# M8320D.net
KiCad netlist of a schematic drawn in EAGLE
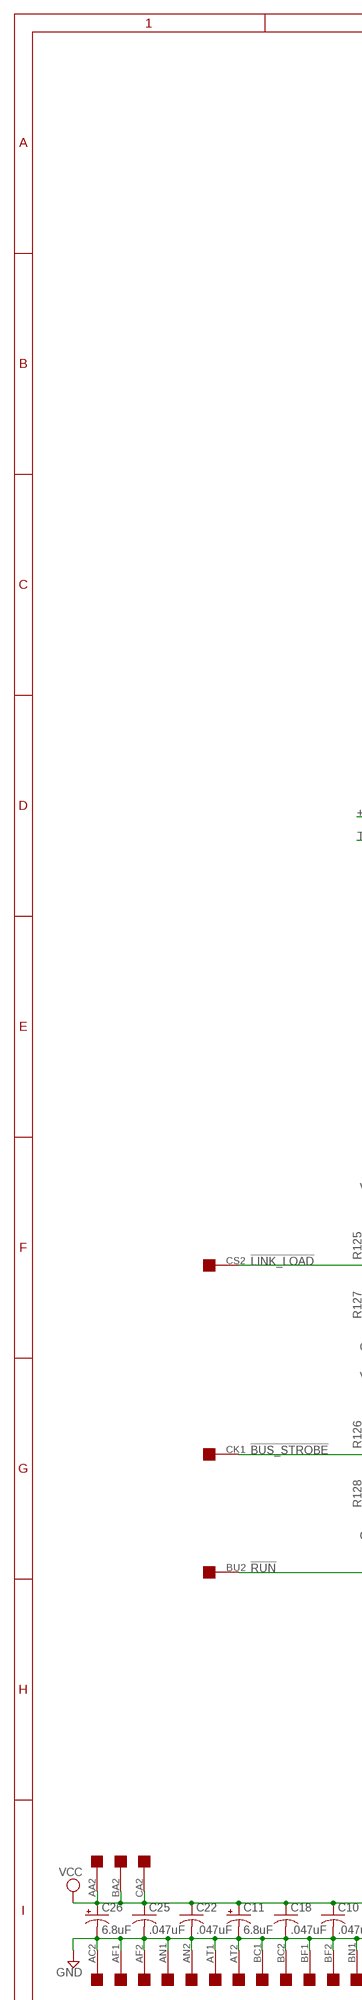
[diagram p0: schematic, sheet 1, part 1 of 2]
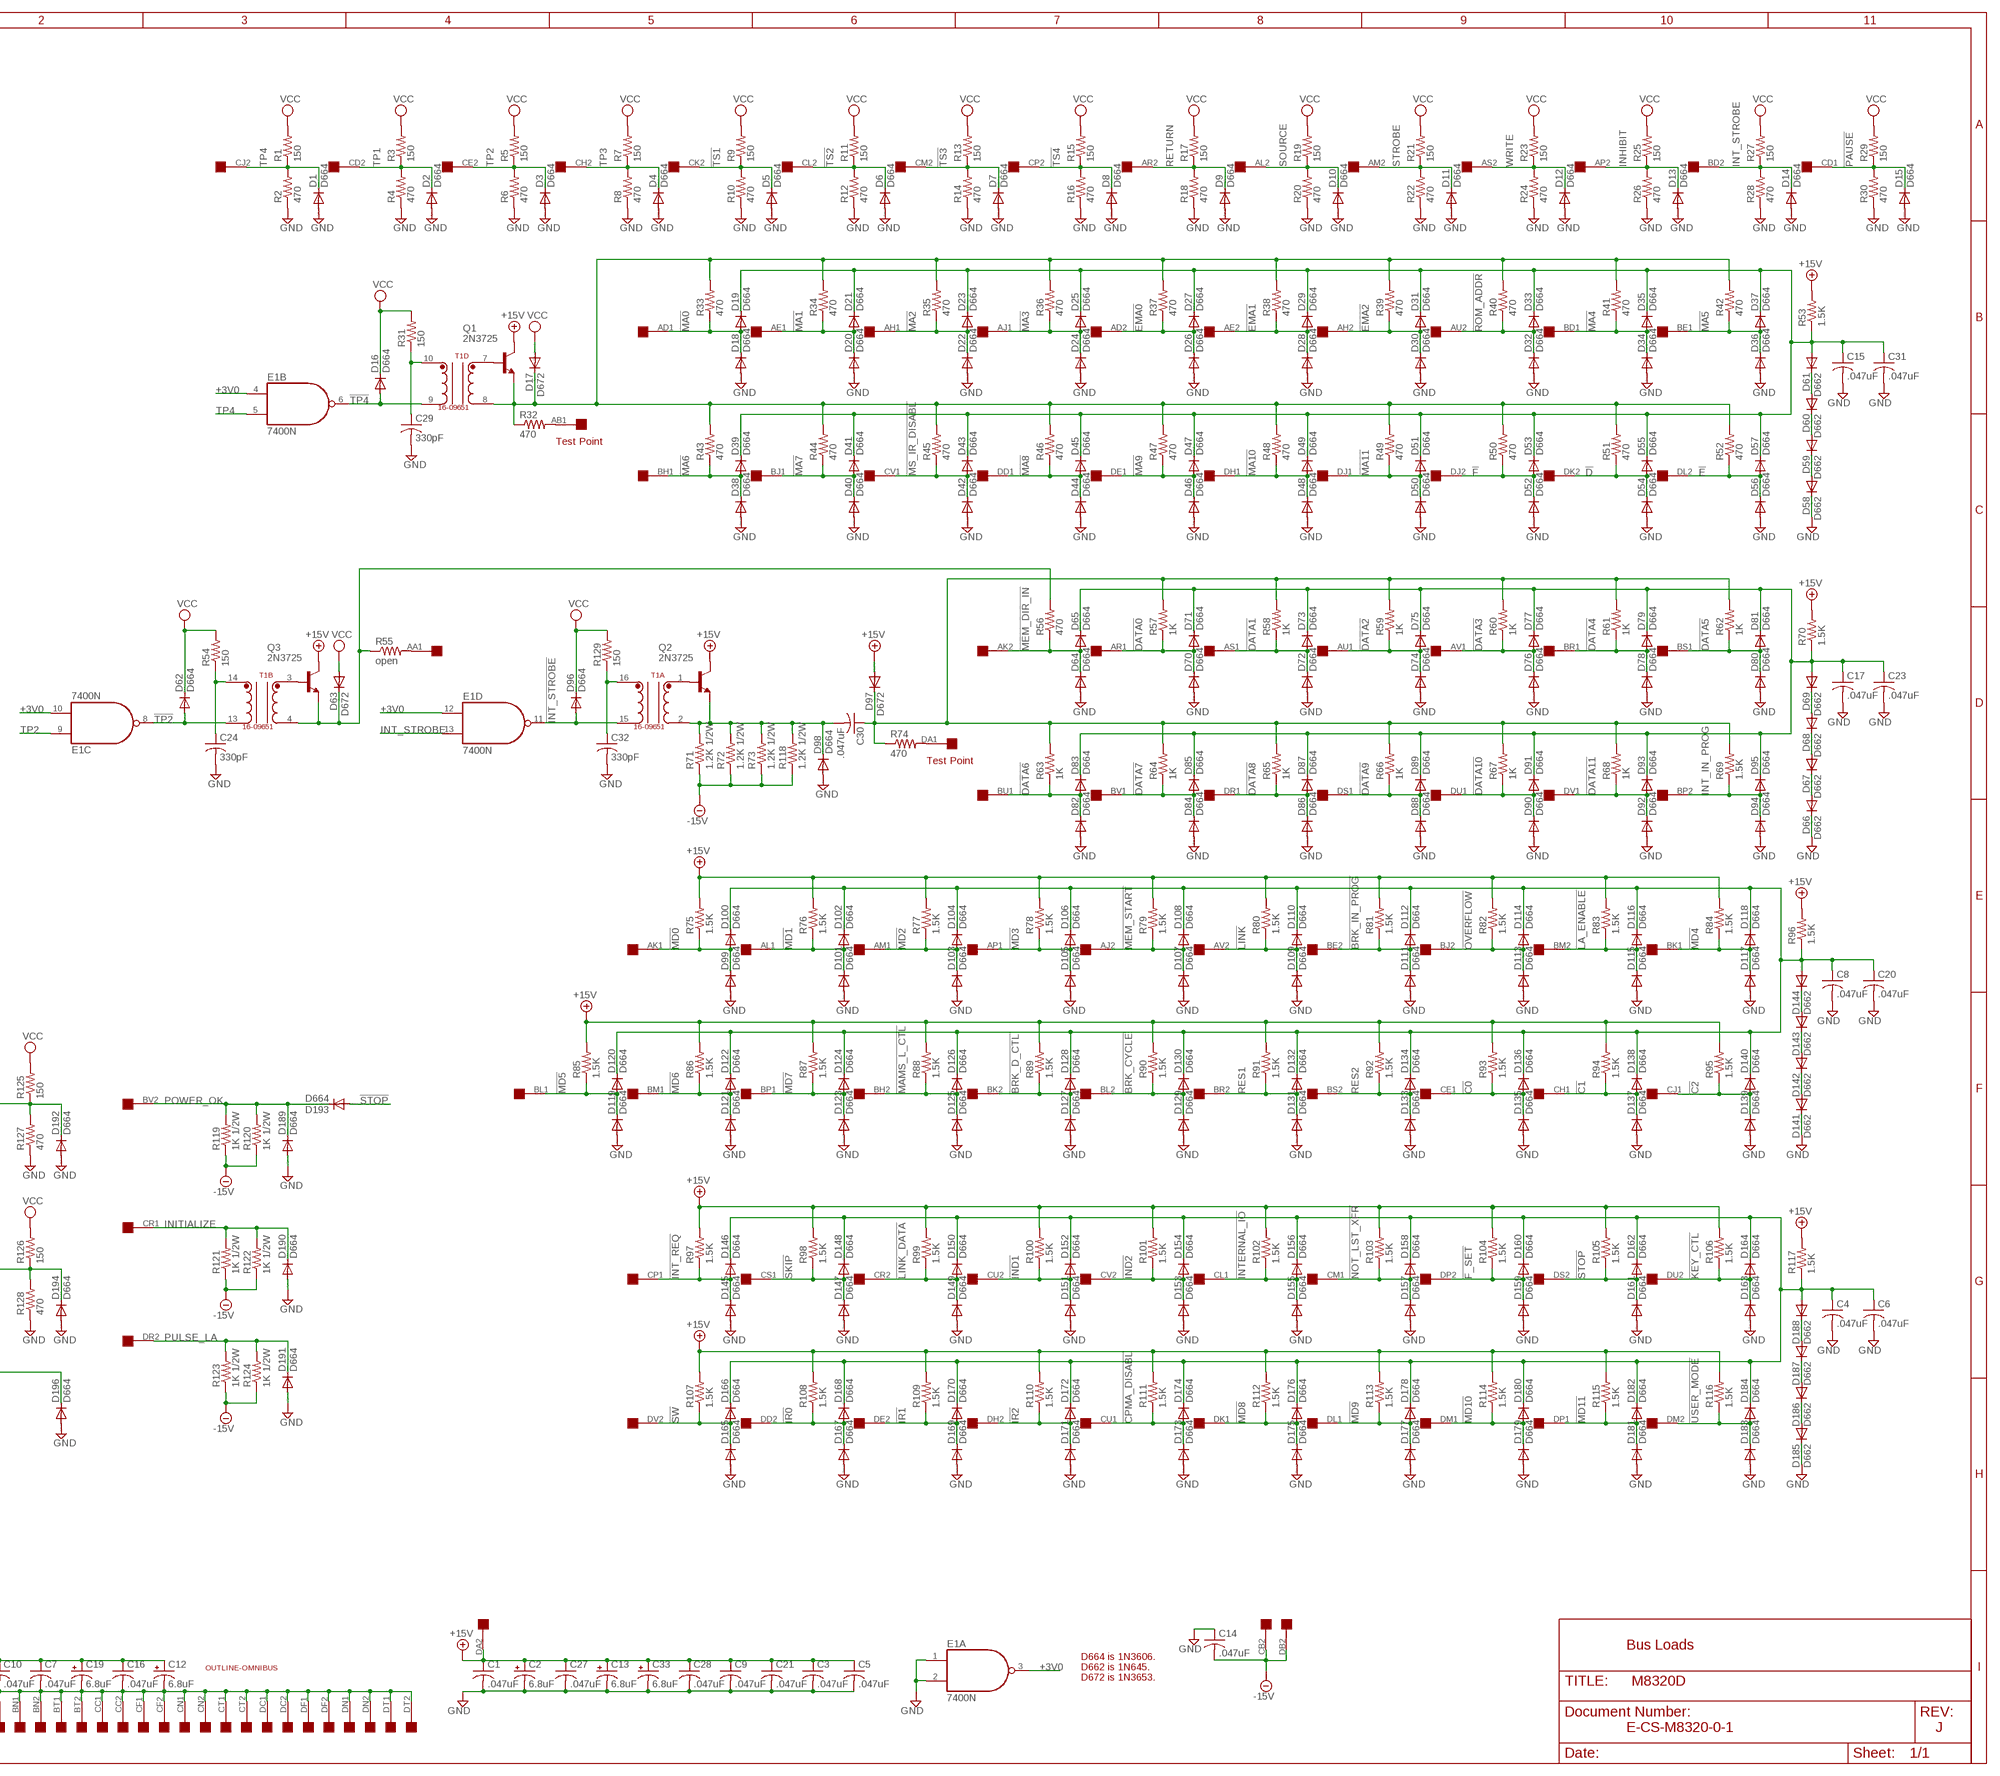
[diagram p1: schematic, sheet 1, part 2 of 2]

(export (version "E")
  (design (tool "Eeschema 10.0.6"))
  (components
    (comp (ref "C1")
      (value ".047uF")
      (footprint "eagle-import:C063-025X075")
      (libsource (lib "eagle-import") (part "C-US"))
    )
    (comp (ref "C2")
      (value "6.8uF")
      (footprint "eagle-import:E12-8")
      (libsource (lib "eagle-import") (part "CPOL-USE20-8AXIAL"))
    )
    (comp (ref "C3")
      (value ".047uF")
      (footprint "eagle-import:C063-025X075")
      (libsource (lib "eagle-import") (part "C-US"))
    )
    (comp (ref "C4")
      (value ".047uF")
      (footprint "eagle-import:C063-025X075")
      (libsource (lib "eagle-import") (part "C-US"))
    )
    (comp (ref "C5")
      (value ".047uF")
      (footprint "eagle-import:C063-025X075")
      (libsource (lib "eagle-import") (part "C-US"))
    )
    (comp (ref "C6")
      (value ".047uF")
      (footprint "eagle-import:C063-025X075")
      (libsource (lib "eagle-import") (part "C-US"))
    )
    (comp (ref "C7")
      (value ".047uF")
      (footprint "eagle-import:C063-025X075")
      (libsource (lib "eagle-import") (part "C-US"))
    )
    (comp (ref "C8")
      (value ".047uF")
      (footprint "eagle-import:C063-025X075")
      (libsource (lib "eagle-import") (part "C-US"))
    )
    (comp (ref "C9")
      (value ".047uF")
      (footprint "eagle-import:C063-025X075")
      (libsource (lib "eagle-import") (part "C-US"))
    )
    (comp (ref "C10")
      (value ".047uF")
      (footprint "eagle-import:C063-025X075")
      (libsource (lib "eagle-import") (part "C-US"))
    )
    (comp (ref "C11")
      (value "6.8uF")
      (footprint "eagle-import:E12-8")
      (libsource (lib "eagle-import") (part "CPOL-USE20-8AXIAL"))
    )
    (comp (ref "C12")
      (value "6.8uF")
      (footprint "eagle-import:E12-8")
      (libsource (lib "eagle-import") (part "CPOL-USE20-8AXIAL"))
    )
    (comp (ref "C13")
      (value "6.8uF")
      (footprint "eagle-import:E12-8")
      (libsource (lib "eagle-import") (part "CPOL-USE20-8AXIAL"))
    )
    (comp (ref "C14")
      (value ".047uF")
      (footprint "eagle-import:C063-025X075")
      (libsource (lib "eagle-import") (part "C-US"))
    )
    (comp (ref "C15")
      (value ".047uF")
      (footprint "eagle-import:C063-025X075")
      (libsource (lib "eagle-import") (part "C-US"))
    )
    (comp (ref "C16")
      (value ".047uF")
      (footprint "eagle-import:C063-025X075")
      (libsource (lib "eagle-import") (part "C-US"))
    )
    (comp (ref "C17")
      (value ".047uF")
      (footprint "eagle-import:C063-025X075")
      (libsource (lib "eagle-import") (part "C-US"))
    )
    (comp (ref "C18")
      (value ".047uF")
      (footprint "eagle-import:C063-025X075")
      (libsource (lib "eagle-import") (part "C-US"))
    )
    (comp (ref "C19")
      (value "6.8uF")
      (footprint "eagle-import:E12-8")
      (libsource (lib "eagle-import") (part "CPOL-USE20-8AXIAL"))
    )
    (comp (ref "C20")
      (value ".047uF")
      (footprint "eagle-import:C063-025X075")
      (libsource (lib "eagle-import") (part "C-US"))
    )
    (comp (ref "C21")
      (value ".047uF")
      (footprint "eagle-import:C063-025X075")
      (libsource (lib "eagle-import") (part "C-US"))
    )
    (comp (ref "C22")
      (value ".047uF")
      (footprint "eagle-import:C063-025X075")
      (libsource (lib "eagle-import") (part "C-US"))
    )
    (comp (ref "C23")
      (value ".047uF")
      (footprint "eagle-import:C063-025X075")
      (libsource (lib "eagle-import") (part "C-US"))
    )
    (comp (ref "C24")
      (value "330pF")
      (footprint "eagle-import:C063-025X075")
      (libsource (lib "eagle-import") (part "C-US"))
    )
    (comp (ref "C25")
      (value ".047uF")
      (footprint "eagle-import:C063-025X075")
      (libsource (lib "eagle-import") (part "C-US"))
    )
    (comp (ref "C26")
      (value "6.8uF")
      (footprint "eagle-import:E12-8")
      (libsource (lib "eagle-import") (part "CPOL-USE20-8AXIAL"))
    )
    (comp (ref "C27")
      (value ".047uF")
      (footprint "eagle-import:C063-025X075")
      (libsource (lib "eagle-import") (part "C-US"))
    )
    (comp (ref "C28")
      (value ".047uF")
      (footprint "eagle-import:C063-025X075")
      (libsource (lib "eagle-import") (part "C-US"))
    )
    (comp (ref "C29")
      (value "330pF")
      (footprint "eagle-import:C063-025X075")
      (libsource (lib "eagle-import") (part "C-US"))
    )
    (comp (ref "C30")
      (value ".047uF")
      (footprint "eagle-import:C063-025X075")
      (libsource (lib "eagle-import") (part "C-US"))
    )
    (comp (ref "C31")
      (value ".047uF")
      (footprint "eagle-import:C063-025X075")
      (libsource (lib "eagle-import") (part "C-US"))
    )
    (comp (ref "C32")
      (value "330pF")
      (footprint "eagle-import:C063-025X075")
      (libsource (lib "eagle-import") (part "C-US"))
    )
    (comp (ref "C33")
      (value "6.8uF")
      (footprint "eagle-import:E12-8")
      (libsource (lib "eagle-import") (part "CPOL-USE20-8AXIAL"))
    )
    (comp (ref "D1")
      (value "D664")
      (footprint "eagle-import:DO35-10")
      (libsource (lib "eagle-import") (part "DIODE-DO35-10"))
    )
    (comp (ref "D2")
      (value "D664")
      (footprint "eagle-import:DO35-10")
      (libsource (lib "eagle-import") (part "DIODE-DO35-10"))
    )
    (comp (ref "D3")
      (value "D664")
      (footprint "eagle-import:DO35-10")
      (libsource (lib "eagle-import") (part "DIODE-DO35-10"))
    )
    (comp (ref "D4")
      (value "D664")
      (footprint "eagle-import:DO35-10")
      (libsource (lib "eagle-import") (part "DIODE-DO35-10"))
    )
    (comp (ref "D5")
      (value "D664")
      (footprint "eagle-import:DO35-10")
      (libsource (lib "eagle-import") (part "DIODE-DO35-10"))
    )
    (comp (ref "D6")
      (value "D664")
      (footprint "eagle-import:DO35-10")
      (libsource (lib "eagle-import") (part "DIODE-DO35-10"))
    )
    (comp (ref "D7")
      (value "D664")
      (footprint "eagle-import:DO35-10")
      (libsource (lib "eagle-import") (part "DIODE-DO35-10"))
    )
    (comp (ref "D8")
      (value "D664")
      (footprint "eagle-import:DO35-10")
      (libsource (lib "eagle-import") (part "DIODE-DO35-10"))
    )
    (comp (ref "D9")
      (value "D664")
      (footprint "eagle-import:DO35-10")
      (libsource (lib "eagle-import") (part "DIODE-DO35-10"))
    )
    (comp (ref "D10")
      (value "D664")
      (footprint "eagle-import:DO35-10")
      (libsource (lib "eagle-import") (part "DIODE-DO35-10"))
    )
    (comp (ref "D11")
      (value "D664")
      (footprint "eagle-import:DO35-10")
      (libsource (lib "eagle-import") (part "DIODE-DO35-10"))
    )
    (comp (ref "D12")
      (value "D664")
      (footprint "eagle-import:DO35-10")
      (libsource (lib "eagle-import") (part "DIODE-DO35-10"))
    )
    (comp (ref "D13")
      (value "D664")
      (footprint "eagle-import:DO35-10")
      (libsource (lib "eagle-import") (part "DIODE-DO35-10"))
    )
    (comp (ref "D14")
      (value "D664")
      (footprint "eagle-import:DO35-10")
      (libsource (lib "eagle-import") (part "DIODE-DO35-10"))
    )
    (comp (ref "D15")
      (value "D664")
      (footprint "eagle-import:DO35-10")
      (libsource (lib "eagle-import") (part "DIODE-DO35-10"))
    )
    (comp (ref "D16")
      (value "D664")
      (footprint "eagle-import:DO35-10")
      (libsource (lib "eagle-import") (part "DIODE-DO35-10"))
    )
    (comp (ref "D17")
      (value "D672")
      (footprint "eagle-import:DO35-10")
      (libsource (lib "eagle-import") (part "DIODE-DO35-10"))
    )
    (comp (ref "D18")
      (value "D664")
      (footprint "eagle-import:DO35-10")
      (libsource (lib "eagle-import") (part "DIODE-DO35-10"))
    )
    (comp (ref "D19")
      (value "D664")
      (footprint "eagle-import:DO35-10")
      (libsource (lib "eagle-import") (part "DIODE-DO35-10"))
    )
    (comp (ref "D20")
      (value "D664")
      (footprint "eagle-import:DO35-10")
      (libsource (lib "eagle-import") (part "DIODE-DO35-10"))
    )
    (comp (ref "D21")
      (value "D664")
      (footprint "eagle-import:DO35-10")
      (libsource (lib "eagle-import") (part "DIODE-DO35-10"))
    )
    (comp (ref "D22")
      (value "D664")
      (footprint "eagle-import:DO35-10")
      (libsource (lib "eagle-import") (part "DIODE-DO35-10"))
    )
    (comp (ref "D23")
      (value "D664")
      (footprint "eagle-import:DO35-10")
      (libsource (lib "eagle-import") (part "DIODE-DO35-10"))
    )
    (comp (ref "D24")
      (value "D664")
      (footprint "eagle-import:DO35-10")
      (libsource (lib "eagle-import") (part "DIODE-DO35-10"))
    )
    (comp (ref "D25")
      (value "D664")
      (footprint "eagle-import:DO35-10")
      (libsource (lib "eagle-import") (part "DIODE-DO35-10"))
    )
    (comp (ref "D26")
      (value "D664")
      (footprint "eagle-import:DO35-10")
      (libsource (lib "eagle-import") (part "DIODE-DO35-10"))
    )
    (comp (ref "D27")
      (value "D664")
      (footprint "eagle-import:DO35-10")
      (libsource (lib "eagle-import") (part "DIODE-DO35-10"))
    )
    (comp (ref "D28")
      (value "D664")
      (footprint "eagle-import:DO35-10")
      (libsource (lib "eagle-import") (part "DIODE-DO35-10"))
    )
    (comp (ref "D29")
      (value "D664")
      (footprint "eagle-import:DO35-10")
      (libsource (lib "eagle-import") (part "DIODE-DO35-10"))
    )
    (comp (ref "D30")
      (value "D664")
      (footprint "eagle-import:DO35-10")
      (libsource (lib "eagle-import") (part "DIODE-DO35-10"))
    )
    (comp (ref "D31")
      (value "D664")
      (footprint "eagle-import:DO35-10")
      (libsource (lib "eagle-import") (part "DIODE-DO35-10"))
    )
    (comp (ref "D32")
      (value "D664")
      (footprint "eagle-import:DO35-10")
      (libsource (lib "eagle-import") (part "DIODE-DO35-10"))
    )
    (comp (ref "D33")
      (value "D664")
      (footprint "eagle-import:DO35-10")
      (libsource (lib "eagle-import") (part "DIODE-DO35-10"))
    )
    (comp (ref "D34")
      (value "D664")
      (footprint "eagle-import:DO35-10")
      (libsource (lib "eagle-import") (part "DIODE-DO35-10"))
    )
    (comp (ref "D35")
      (value "D664")
      (footprint "eagle-import:DO35-10")
      (libsource (lib "eagle-import") (part "DIODE-DO35-10"))
    )
    (comp (ref "D36")
      (value "D664")
      (footprint "eagle-import:DO35-10")
      (libsource (lib "eagle-import") (part "DIODE-DO35-10"))
    )
    (comp (ref "D37")
      (value "D664")
      (footprint "eagle-import:DO35-10")
      (libsource (lib "eagle-import") (part "DIODE-DO35-10"))
    )
    (comp (ref "D38")
      (value "D664")
      (footprint "eagle-import:DO35-10")
      (libsource (lib "eagle-import") (part "DIODE-DO35-10"))
    )
    (comp (ref "D39")
      (value "D664")
      (footprint "eagle-import:DO35-10")
      (libsource (lib "eagle-import") (part "DIODE-DO35-10"))
    )
    (comp (ref "D40")
      (value "D664")
      (footprint "eagle-import:DO35-10")
      (libsource (lib "eagle-import") (part "DIODE-DO35-10"))
    )
    (comp (ref "D41")
      (value "D664")
      (footprint "eagle-import:DO35-10")
      (libsource (lib "eagle-import") (part "DIODE-DO35-10"))
    )
    (comp (ref "D42")
      (value "D664")
      (footprint "eagle-import:DO35-10")
      (libsource (lib "eagle-import") (part "DIODE-DO35-10"))
    )
    (comp (ref "D43")
      (value "D664")
      (footprint "eagle-import:DO35-10")
      (libsource (lib "eagle-import") (part "DIODE-DO35-10"))
    )
    (comp (ref "D44")
      (value "D664")
      (footprint "eagle-import:DO35-10")
      (libsource (lib "eagle-import") (part "DIODE-DO35-10"))
    )
    (comp (ref "D45")
      (value "D664")
      (footprint "eagle-import:DO35-10")
      (libsource (lib "eagle-import") (part "DIODE-DO35-10"))
    )
    (comp (ref "D46")
      (value "D664")
      (footprint "eagle-import:DO35-10")
      (libsource (lib "eagle-import") (part "DIODE-DO35-10"))
    )
    (comp (ref "D47")
      (value "D664")
      (footprint "eagle-import:DO35-10")
      (libsource (lib "eagle-import") (part "DIODE-DO35-10"))
    )
    (comp (ref "D48")
      (value "D664")
      (footprint "eagle-import:DO35-10")
      (libsource (lib "eagle-import") (part "DIODE-DO35-10"))
    )
    (comp (ref "D49")
      (value "D664")
      (footprint "eagle-import:DO35-10")
      (libsource (lib "eagle-import") (part "DIODE-DO35-10"))
    )
    (comp (ref "D50")
      (value "D664")
      (footprint "eagle-import:DO35-10")
      (libsource (lib "eagle-import") (part "DIODE-DO35-10"))
    )
    (comp (ref "D51")
      (value "D664")
      (footprint "eagle-import:DO35-10")
      (libsource (lib "eagle-import") (part "DIODE-DO35-10"))
    )
    (comp (ref "D52")
      (value "D664")
      (footprint "eagle-import:DO35-10")
      (libsource (lib "eagle-import") (part "DIODE-DO35-10"))
    )
    (comp (ref "D53")
      (value "D664")
      (footprint "eagle-import:DO35-10")
      (libsource (lib "eagle-import") (part "DIODE-DO35-10"))
    )
    (comp (ref "D54")
      (value "D664")
      (footprint "eagle-import:DO35-10")
      (libsource (lib "eagle-import") (part "DIODE-DO35-10"))
    )
    (comp (ref "D55")
      (value "D664")
      (footprint "eagle-import:DO35-10")
      (libsource (lib "eagle-import") (part "DIODE-DO35-10"))
    )
    (comp (ref "D56")
      (value "D664")
      (footprint "eagle-import:DO35-10")
      (libsource (lib "eagle-import") (part "DIODE-DO35-10"))
    )
    (comp (ref "D57")
      (value "D664")
      (footprint "eagle-import:DO35-10")
      (libsource (lib "eagle-import") (part "DIODE-DO35-10"))
    )
    (comp (ref "D58")
      (value "D662")
      (footprint "eagle-import:DO35-10")
      (libsource (lib "eagle-import") (part "DIODE-DO35-10"))
    )
    (comp (ref "D59")
      (value "D662")
      (footprint "eagle-import:DO35-10")
      (libsource (lib "eagle-import") (part "DIODE-DO35-10"))
    )
    (comp (ref "D60")
      (value "D662")
      (footprint "eagle-import:DO35-10")
      (libsource (lib "eagle-import") (part "DIODE-DO35-10"))
    )
    (comp (ref "D61")
      (value "D662")
      (footprint "eagle-import:DO35-10")
      (libsource (lib "eagle-import") (part "DIODE-DO35-10"))
    )
    (comp (ref "D62")
      (value "D664")
      (footprint "eagle-import:DO35-10")
      (libsource (lib "eagle-import") (part "DIODE-DO35-10"))
    )
    (comp (ref "D63")
      (value "D672")
      (footprint "eagle-import:DO35-10")
      (libsource (lib "eagle-import") (part "DIODE-DO35-10"))
    )
    (comp (ref "D64")
      (value "D664")
      (footprint "eagle-import:DO35-10")
      (libsource (lib "eagle-import") (part "DIODE-DO35-10"))
    )
    (comp (ref "D65")
      (value "D664")
      (footprint "eagle-import:DO35-10")
      (libsource (lib "eagle-import") (part "DIODE-DO35-10"))
    )
    (comp (ref "D66")
      (value "D662")
      (footprint "eagle-import:DO35-10")
      (libsource (lib "eagle-import") (part "DIODE-DO35-10"))
    )
    (comp (ref "D67")
      (value "D662")
      (footprint "eagle-import:DO35-10")
      (libsource (lib "eagle-import") (part "DIODE-DO35-10"))
    )
    (comp (ref "D68")
      (value "D662")
      (footprint "eagle-import:DO35-10")
      (libsource (lib "eagle-import") (part "DIODE-DO35-10"))
    )
    (comp (ref "D69")
      (value "D662")
      (footprint "eagle-import:DO35-10")
      (libsource (lib "eagle-import") (part "DIODE-DO35-10"))
    )
    (comp (ref "D70")
      (value "D664")
      (footprint "eagle-import:DO35-10")
      (libsource (lib "eagle-import") (part "DIODE-DO35-10"))
    )
    (comp (ref "D71")
      (value "D664")
      (footprint "eagle-import:DO35-10")
      (libsource (lib "eagle-import") (part "DIODE-DO35-10"))
    )
    (comp (ref "D72")
      (value "D664")
      (footprint "eagle-import:DO35-10")
      (libsource (lib "eagle-import") (part "DIODE-DO35-10"))
    )
    (comp (ref "D73")
      (value "D664")
      (footprint "eagle-import:DO35-10")
      (libsource (lib "eagle-import") (part "DIODE-DO35-10"))
    )
    (comp (ref "D74")
      (value "D664")
      (footprint "eagle-import:DO35-10")
      (libsource (lib "eagle-import") (part "DIODE-DO35-10"))
    )
    (comp (ref "D75")
      (value "D664")
      (footprint "eagle-import:DO35-10")
      (libsource (lib "eagle-import") (part "DIODE-DO35-10"))
    )
    (comp (ref "D76")
      (value "D664")
      (footprint "eagle-import:DO35-10")
      (libsource (lib "eagle-import") (part "DIODE-DO35-10"))
    )
    (comp (ref "D77")
      (value "D664")
      (footprint "eagle-import:DO35-10")
      (libsource (lib "eagle-import") (part "DIODE-DO35-10"))
    )
    (comp (ref "D78")
      (value "D664")
      (footprint "eagle-import:DO35-10")
      (libsource (lib "eagle-import") (part "DIODE-DO35-10"))
    )
    (comp (ref "D79")
      (value "D664")
      (footprint "eagle-import:DO35-10")
      (libsource (lib "eagle-import") (part "DIODE-DO35-10"))
    )
    (comp (ref "D80")
      (value "D664")
      (footprint "eagle-import:DO35-10")
      (libsource (lib "eagle-import") (part "DIODE-DO35-10"))
    )
    (comp (ref "D81")
      (value "D664")
      (footprint "eagle-import:DO35-10")
      (libsource (lib "eagle-import") (part "DIODE-DO35-10"))
    )
    (comp (ref "D82")
      (value "D664")
      (footprint "eagle-import:DO35-10")
      (libsource (lib "eagle-import") (part "DIODE-DO35-10"))
    )
    (comp (ref "D83")
      (value "D664")
      (footprint "eagle-import:DO35-10")
      (libsource (lib "eagle-import") (part "DIODE-DO35-10"))
    )
    (comp (ref "D84")
      (value "D664")
      (footprint "eagle-import:DO35-10")
      (libsource (lib "eagle-import") (part "DIODE-DO35-10"))
    )
    (comp (ref "D85")
      (value "D664")
      (footprint "eagle-import:DO35-10")
      (libsource (lib "eagle-import") (part "DIODE-DO35-10"))
    )
    (comp (ref "D86")
      (value "D664")
      (footprint "eagle-import:DO35-10")
      (libsource (lib "eagle-import") (part "DIODE-DO35-10"))
    )
    (comp (ref "D87")
      (value "D664")
      (footprint "eagle-import:DO35-10")
      (libsource (lib "eagle-import") (part "DIODE-DO35-10"))
    )
    (comp (ref "D88")
      (value "D664")
      (footprint "eagle-import:DO35-10")
      (libsource (lib "eagle-import") (part "DIODE-DO35-10"))
    )
    (comp (ref "D89")
      (value "D664")
      (footprint "eagle-import:DO35-10")
      (libsource (lib "eagle-import") (part "DIODE-DO35-10"))
    )
    (comp (ref "D90")
      (value "D664")
      (footprint "eagle-import:DO35-10")
      (libsource (lib "eagle-import") (part "DIODE-DO35-10"))
    )
    (comp (ref "D91")
      (value "D664")
      (footprint "eagle-import:DO35-10")
      (libsource (lib "eagle-import") (part "DIODE-DO35-10"))
    )
    (comp (ref "D92")
      (value "D664")
      (footprint "eagle-import:DO35-10")
      (libsource (lib "eagle-import") (part "DIODE-DO35-10"))
    )
    (comp (ref "D93")
      (value "D664")
      (footprint "eagle-import:DO35-10")
      (libsource (lib "eagle-import") (part "DIODE-DO35-10"))
    )
    (comp (ref "D94")
      (value "D664")
      (footprint "eagle-import:DO35-10")
      (libsource (lib "eagle-import") (part "DIODE-DO35-10"))
    )
    (comp (ref "D95")
      (value "D664")
      (footprint "eagle-import:DO35-10")
      (libsource (lib "eagle-import") (part "DIODE-DO35-10"))
    )
    (comp (ref "D96")
      (value "D664")
      (footprint "eagle-import:DO35-10")
      (libsource (lib "eagle-import") (part "DIODE-DO35-10"))
    )
    (comp (ref "D97")
      (value "D672")
      (footprint "eagle-import:DO35-10")
      (libsource (lib "eagle-import") (part "DIODE-DO35-10"))
    )
    (comp (ref "D98")
      (value "D664")
      (footprint "eagle-import:DO35-10")
      (libsource (lib "eagle-import") (part "DIODE-DO35-10"))
    )
    (comp (ref "D99")
      (value "D664")
      (footprint "eagle-import:DO35-10")
      (libsource (lib "eagle-import") (part "DIODE-DO35-10"))
    )
    (comp (ref "D100")
      (value "D664")
      (footprint "eagle-import:DO35-10")
      (libsource (lib "eagle-import") (part "DIODE-DO35-10"))
    )
    (comp (ref "D101")
      (value "D664")
      (footprint "eagle-import:DO35-10")
      (libsource (lib "eagle-import") (part "DIODE-DO35-10"))
    )
    (comp (ref "D102")
      (value "D664")
      (footprint "eagle-import:DO35-10")
      (libsource (lib "eagle-import") (part "DIODE-DO35-10"))
    )
    (comp (ref "D103")
      (value "D664")
      (footprint "eagle-import:DO35-10")
      (libsource (lib "eagle-import") (part "DIODE-DO35-10"))
    )
    (comp (ref "D104")
      (value "D664")
      (footprint "eagle-import:DO35-10")
      (libsource (lib "eagle-import") (part "DIODE-DO35-10"))
    )
    (comp (ref "D105")
      (value "D664")
      (footprint "eagle-import:DO35-10")
      (libsource (lib "eagle-import") (part "DIODE-DO35-10"))
    )
    (comp (ref "D106")
      (value "D664")
      (footprint "eagle-import:DO35-10")
      (libsource (lib "eagle-import") (part "DIODE-DO35-10"))
    )
    (comp (ref "D107")
      (value "D664")
      (footprint "eagle-import:DO35-10")
      (libsource (lib "eagle-import") (part "DIODE-DO35-10"))
    )
    (comp (ref "D108")
      (value "D664")
      (footprint "eagle-import:DO35-10")
      (libsource (lib "eagle-import") (part "DIODE-DO35-10"))
    )
    (comp (ref "D109")
      (value "D664")
      (footprint "eagle-import:DO35-10")
      (libsource (lib "eagle-import") (part "DIODE-DO35-10"))
    )
    (comp (ref "D110")
      (value "D664")
      (footprint "eagle-import:DO35-10")
      (libsource (lib "eagle-import") (part "DIODE-DO35-10"))
    )
    (comp (ref "D111")
      (value "D664")
      (footprint "eagle-import:DO35-10")
      (libsource (lib "eagle-import") (part "DIODE-DO35-10"))
    )
    (comp (ref "D112")
      (value "D664")
      (footprint "eagle-import:DO35-10")
      (libsource (lib "eagle-import") (part "DIODE-DO35-10"))
    )
    (comp (ref "D113")
      (value "D664")
      (footprint "eagle-import:DO35-10")
      (libsource (lib "eagle-import") (part "DIODE-DO35-10"))
    )
    (comp (ref "D114")
      (value "D664")
      (footprint "eagle-import:DO35-10")
      (libsource (lib "eagle-import") (part "DIODE-DO35-10"))
    )
    (comp (ref "D115")
      (value "D664")
      (footprint "eagle-import:DO35-10")
      (libsource (lib "eagle-import") (part "DIODE-DO35-10"))
    )
    (comp (ref "D116")
      (value "D664")
      (footprint "eagle-import:DO35-10")
      (libsource (lib "eagle-import") (part "DIODE-DO35-10"))
    )
    (comp (ref "D117")
      (value "D664")
      (footprint "eagle-import:DO35-10")
      (libsource (lib "eagle-import") (part "DIODE-DO35-10"))
    )
    (comp (ref "D118")
      (value "D664")
      (footprint "eagle-import:DO35-10")
      (libsource (lib "eagle-import") (part "DIODE-DO35-10"))
    )
    (comp (ref "D119")
      (value "D664")
      (footprint "eagle-import:DO35-10")
      (libsource (lib "eagle-import") (part "DIODE-DO35-10"))
    )
    (comp (ref "D120")
      (value "D664")
      (footprint "eagle-import:DO35-10")
      (libsource (lib "eagle-import") (part "DIODE-DO35-10"))
    )
    (comp (ref "D121")
      (value "D664")
      (footprint "eagle-import:DO35-10")
      (libsource (lib "eagle-import") (part "DIODE-DO35-10"))
    )
    (comp (ref "D122")
      (value "D664")
      (footprint "eagle-import:DO35-10")
      (libsource (lib "eagle-import") (part "DIODE-DO35-10"))
    )
    (comp (ref "D123")
      (value "D664")
      (footprint "eagle-import:DO35-10")
      (libsource (lib "eagle-import") (part "DIODE-DO35-10"))
    )
    (comp (ref "D124")
      (value "D664")
      (footprint "eagle-import:DO35-10")
      (libsource (lib "eagle-import") (part "DIODE-DO35-10"))
    )
    (comp (ref "D125")
      (value "D664")
      (footprint "eagle-import:DO35-10")
      (libsource (lib "eagle-import") (part "DIODE-DO35-10"))
    )
    (comp (ref "D126")
      (value "D664")
      (footprint "eagle-import:DO35-10")
      (libsource (lib "eagle-import") (part "DIODE-DO35-10"))
    )
    (comp (ref "D127")
      (value "D664")
      (footprint "eagle-import:DO35-10")
      (libsource (lib "eagle-import") (part "DIODE-DO35-10"))
    )
    (comp (ref "D128")
      (value "D664")
      (footprint "eagle-import:DO35-10")
      (libsource (lib "eagle-import") (part "DIODE-DO35-10"))
    )
    (comp (ref "D129")
      (value "D664")
      (footprint "eagle-import:DO35-10")
      (libsource (lib "eagle-import") (part "DIODE-DO35-10"))
    )
    (comp (ref "D130")
      (value "D664")
      (footprint "eagle-import:DO35-10")
      (libsource (lib "eagle-import") (part "DIODE-DO35-10"))
    )
    (comp (ref "D131")
      (value "D664")
      (footprint "eagle-import:DO35-10")
      (libsource (lib "eagle-import") (part "DIODE-DO35-10"))
    )
    (comp (ref "D132")
      (value "D664")
      (footprint "eagle-import:DO35-10")
      (libsource (lib "eagle-import") (part "DIODE-DO35-10"))
    )
    (comp (ref "D133")
      (value "D664")
      (footprint "eagle-import:DO35-10")
      (libsource (lib "eagle-import") (part "DIODE-DO35-10"))
    )
    (comp (ref "D134")
      (value "D664")
      (footprint "eagle-import:DO35-10")
      (libsource (lib "eagle-import") (part "DIODE-DO35-10"))
    )
    (comp (ref "D135")
      (value "D664")
      (footprint "eagle-import:DO35-10")
      (libsource (lib "eagle-import") (part "DIODE-DO35-10"))
    )
    (comp (ref "D136")
      (value "D664")
      (footprint "eagle-import:DO35-10")
      (libsource (lib "eagle-import") (part "DIODE-DO35-10"))
    )
    (comp (ref "D137")
      (value "D664")
      (footprint "eagle-import:DO35-10")
      (libsource (lib "eagle-import") (part "DIODE-DO35-10"))
    )
    (comp (ref "D138")
      (value "D664")
      (footprint "eagle-import:DO35-10")
      (libsource (lib "eagle-import") (part "DIODE-DO35-10"))
    )
    (comp (ref "D139")
      (value "D664")
      (footprint "eagle-import:DO35-10")
      (libsource (lib "eagle-import") (part "DIODE-DO35-10"))
    )
    (comp (ref "D140")
      (value "D664")
      (footprint "eagle-import:DO35-10")
      (libsource (lib "eagle-import") (part "DIODE-DO35-10"))
    )
    (comp (ref "D141")
      (value "D662")
      (footprint "eagle-import:DO35-10")
      (libsource (lib "eagle-import") (part "DIODE-DO35-10"))
    )
    (comp (ref "D142")
      (value "D662")
      (footprint "eagle-import:DO35-10")
      (libsource (lib "eagle-import") (part "DIODE-DO35-10"))
    )
    (comp (ref "D143")
      (value "D662")
      (footprint "eagle-import:DO35-10")
      (libsource (lib "eagle-import") (part "DIODE-DO35-10"))
    )
    (comp (ref "D144")
      (value "D662")
      (footprint "eagle-import:DO35-10")
      (libsource (lib "eagle-import") (part "DIODE-DO35-10"))
    )
    (comp (ref "D145")
      (value "D664")
      (footprint "eagle-import:DO35-10")
      (libsource (lib "eagle-import") (part "DIODE-DO35-10"))
    )
    (comp (ref "D146")
      (value "D664")
      (footprint "eagle-import:DO35-10")
      (libsource (lib "eagle-import") (part "DIODE-DO35-10"))
    )
    (comp (ref "D147")
      (value "D664")
      (footprint "eagle-import:DO35-10")
      (libsource (lib "eagle-import") (part "DIODE-DO35-10"))
    )
    (comp (ref "D148")
      (value "D664")
      (footprint "eagle-import:DO35-10")
      (libsource (lib "eagle-import") (part "DIODE-DO35-10"))
    )
    (comp (ref "D149")
      (value "D664")
      (footprint "eagle-import:DO35-10")
      (libsource (lib "eagle-import") (part "DIODE-DO35-10"))
    )
    (comp (ref "D150")
      (value "D664")
      (footprint "eagle-import:DO35-10")
      (libsource (lib "eagle-import") (part "DIODE-DO35-10"))
    )
    (comp (ref "D151")
      (value "D664")
      (footprint "eagle-import:DO35-10")
      (libsource (lib "eagle-import") (part "DIODE-DO35-10"))
    )
    (comp (ref "D152")
      (value "D664")
      (footprint "eagle-import:DO35-10")
      (libsource (lib "eagle-import") (part "DIODE-DO35-10"))
    )
    (comp (ref "D153")
      (value "D664")
      (footprint "eagle-import:DO35-10")
      (libsource (lib "eagle-import") (part "DIODE-DO35-10"))
    )
    (comp (ref "D154")
      (value "D664")
      (footprint "eagle-import:DO35-10")
      (libsource (lib "eagle-import") (part "DIODE-DO35-10"))
    )
    (comp (ref "D155")
      (value "D664")
      (footprint "eagle-import:DO35-10")
      (libsource (lib "eagle-import") (part "DIODE-DO35-10"))
    )
    (comp (ref "D156")
      (value "D664")
      (footprint "eagle-import:DO35-10")
      (libsource (lib "eagle-import") (part "DIODE-DO35-10"))
    )
    (comp (ref "D157")
      (value "D664")
      (footprint "eagle-import:DO35-10")
      (libsource (lib "eagle-import") (part "DIODE-DO35-10"))
    )
    (comp (ref "D158")
      (value "D664")
      (footprint "eagle-import:DO35-10")
      (libsource (lib "eagle-import") (part "DIODE-DO35-10"))
    )
    (comp (ref "D159")
      (value "D664")
      (footprint "eagle-import:DO35-10")
      (libsource (lib "eagle-import") (part "DIODE-DO35-10"))
    )
    (comp (ref "D160")
      (value "D664")
      (footprint "eagle-import:DO35-10")
      (libsource (lib "eagle-import") (part "DIODE-DO35-10"))
    )
    (comp (ref "D161")
      (value "D664")
      (footprint "eagle-import:DO35-10")
      (libsource (lib "eagle-import") (part "DIODE-DO35-10"))
    )
    (comp (ref "D162")
      (value "D664")
      (footprint "eagle-import:DO35-10")
      (libsource (lib "eagle-import") (part "DIODE-DO35-10"))
    )
    (comp (ref "D163")
      (value "D664")
      (footprint "eagle-import:DO35-10")
      (libsource (lib "eagle-import") (part "DIODE-DO35-10"))
    )
    (comp (ref "D164")
      (value "D664")
      (footprint "eagle-import:DO35-10")
      (libsource (lib "eagle-import") (part "DIODE-DO35-10"))
    )
    (comp (ref "D165")
      (value "D664")
      (footprint "eagle-import:DO35-10")
      (libsource (lib "eagle-import") (part "DIODE-DO35-10"))
    )
    (comp (ref "D166")
      (value "D664")
      (footprint "eagle-import:DO35-10")
      (libsource (lib "eagle-import") (part "DIODE-DO35-10"))
    )
    (comp (ref "D167")
      (value "D664")
      (footprint "eagle-import:DO35-10")
      (libsource (lib "eagle-import") (part "DIODE-DO35-10"))
    )
    (comp (ref "D168")
      (value "D664")
      (footprint "eagle-import:DO35-10")
      (libsource (lib "eagle-import") (part "DIODE-DO35-10"))
    )
    (comp (ref "D169")
      (value "D664")
      (footprint "eagle-import:DO35-10")
      (libsource (lib "eagle-import") (part "DIODE-DO35-10"))
    )
    (comp (ref "D170")
      (value "D664")
      (footprint "eagle-import:DO35-10")
      (libsource (lib "eagle-import") (part "DIODE-DO35-10"))
    )
    (comp (ref "D171")
      (value "D664")
      (footprint "eagle-import:DO35-10")
      (libsource (lib "eagle-import") (part "DIODE-DO35-10"))
    )
    (comp (ref "D172")
      (value "D664")
      (footprint "eagle-import:DO35-10")
      (libsource (lib "eagle-import") (part "DIODE-DO35-10"))
    )
    (comp (ref "D173")
      (value "D664")
      (footprint "eagle-import:DO35-10")
      (libsource (lib "eagle-import") (part "DIODE-DO35-10"))
    )
    (comp (ref "D174")
      (value "D664")
      (footprint "eagle-import:DO35-10")
      (libsource (lib "eagle-import") (part "DIODE-DO35-10"))
    )
    (comp (ref "D175")
      (value "D664")
      (footprint "eagle-import:DO35-10")
      (libsource (lib "eagle-import") (part "DIODE-DO35-10"))
    )
    (comp (ref "D176")
      (value "D664")
      (footprint "eagle-import:DO35-10")
      (libsource (lib "eagle-import") (part "DIODE-DO35-10"))
    )
    (comp (ref "D177")
      (value "D664")
      (footprint "eagle-import:DO35-10")
      (libsource (lib "eagle-import") (part "DIODE-DO35-10"))
    )
    (comp (ref "D178")
      (value "D664")
      (footprint "eagle-import:DO35-10")
      (libsource (lib "eagle-import") (part "DIODE-DO35-10"))
    )
    (comp (ref "D179")
      (value "D664")
      (footprint "eagle-import:DO35-10")
      (libsource (lib "eagle-import") (part "DIODE-DO35-10"))
    )
    (comp (ref "D180")
      (value "D664")
      (footprint "eagle-import:DO35-10")
      (libsource (lib "eagle-import") (part "DIODE-DO35-10"))
    )
    (comp (ref "D181")
      (value "D664")
      (footprint "eagle-import:DO35-10")
      (libsource (lib "eagle-import") (part "DIODE-DO35-10"))
    )
    (comp (ref "D182")
      (value "D664")
      (footprint "eagle-import:DO35-10")
      (libsource (lib "eagle-import") (part "DIODE-DO35-10"))
    )
    (comp (ref "D183")
      (value "D664")
      (footprint "eagle-import:DO35-10")
      (libsource (lib "eagle-import") (part "DIODE-DO35-10"))
    )
    (comp (ref "D184")
      (value "D664")
      (footprint "eagle-import:DO35-10")
      (libsource (lib "eagle-import") (part "DIODE-DO35-10"))
    )
    (comp (ref "D185")
      (value "D662")
      (footprint "eagle-import:DO35-10")
      (libsource (lib "eagle-import") (part "DIODE-DO35-10"))
    )
    (comp (ref "D186")
      (value "D662")
      (footprint "eagle-import:DO35-10")
      (libsource (lib "eagle-import") (part "DIODE-DO35-10"))
    )
    (comp (ref "D187")
      (value "D662")
      (footprint "eagle-import:DO35-10")
      (libsource (lib "eagle-import") (part "DIODE-DO35-10"))
    )
    (comp (ref "D188")
      (value "D662")
      (footprint "eagle-import:DO35-10")
      (libsource (lib "eagle-import") (part "DIODE-DO35-10"))
    )
    (comp (ref "D189")
      (value "D664")
      (footprint "eagle-import:DO35-10")
      (libsource (lib "eagle-import") (part "DIODE-DO35-10"))
    )
    (comp (ref "D190")
      (value "D664")
      (footprint "eagle-import:DO35-10")
      (libsource (lib "eagle-import") (part "DIODE-DO35-10"))
    )
    (comp (ref "D191")
      (value "D664")
      (footprint "eagle-import:DO35-10")
      (libsource (lib "eagle-import") (part "DIODE-DO35-10"))
    )
    (comp (ref "D192")
      (value "D664")
      (footprint "eagle-import:DO35-10")
      (libsource (lib "eagle-import") (part "DIODE-DO35-10"))
    )
    (comp (ref "D193")
      (value "D664")
      (footprint "eagle-import:DO35-10")
      (libsource (lib "eagle-import") (part "DIODE-DO35-10"))
    )
    (comp (ref "D194")
      (value "D664")
      (footprint "eagle-import:DO35-10")
      (libsource (lib "eagle-import") (part "DIODE-DO35-10"))
    )
    (comp (ref "D196")
      (value "D664")
      (footprint "eagle-import:DO35-10")
      (libsource (lib "eagle-import") (part "DIODE-DO35-10"))
    )
    (comp (ref "E1")
      (value "7400N")
      (footprint "eagle-import:DIL14")
      (libsource (lib "eagle-import") (part "7400N"))
    )
    (comp (ref "Q1")
      (value "2N3725")
      (footprint "eagle-import:TO92-EBC")
      (libsource (lib "eagle-import") (part "-NPN-TO92-EBC"))
    )
    (comp (ref "Q2")
      (value "2N3725")
      (footprint "eagle-import:TO92-EBC")
      (libsource (lib "eagle-import") (part "-NPN-TO92-EBC"))
    )
    (comp (ref "Q3")
      (value "2N3725")
      (footprint "eagle-import:TO92-EBC")
      (libsource (lib "eagle-import") (part "-NPN-TO92-EBC"))
    )
    (comp (ref "R1")
      (value "150")
      (footprint "eagle-import:0207_10")
      (libsource (lib "eagle-import") (part "R-US_0207/10"))
    )
    (comp (ref "R2")
      (value "470")
      (footprint "eagle-import:0207_10")
      (libsource (lib "eagle-import") (part "R-US_0207/10"))
    )
    (comp (ref "R3")
      (value "150")
      (footprint "eagle-import:0207_10")
      (libsource (lib "eagle-import") (part "R-US_0207/10"))
    )
    (comp (ref "R4")
      (value "470")
      (footprint "eagle-import:0207_10")
      (libsource (lib "eagle-import") (part "R-US_0207/10"))
    )
    (comp (ref "R5")
      (value "150")
      (footprint "eagle-import:0207_10")
      (libsource (lib "eagle-import") (part "R-US_0207/10"))
    )
    (comp (ref "R6")
      (value "470")
      (footprint "eagle-import:0207_10")
      (libsource (lib "eagle-import") (part "R-US_0207/10"))
    )
    (comp (ref "R7")
      (value "150")
      (footprint "eagle-import:0207_10")
      (libsource (lib "eagle-import") (part "R-US_0207/10"))
    )
    (comp (ref "R8")
      (value "470")
      (footprint "eagle-import:0207_10")
      (libsource (lib "eagle-import") (part "R-US_0207/10"))
    )
    (comp (ref "R9")
      (value "150")
      (footprint "eagle-import:0207_10")
      (libsource (lib "eagle-import") (part "R-US_0207/10"))
    )
    (comp (ref "R10")
      (value "470")
      (footprint "eagle-import:0207_10")
      (libsource (lib "eagle-import") (part "R-US_0207/10"))
    )
    (comp (ref "R11")
      (value "150")
      (footprint "eagle-import:0207_10")
      (libsource (lib "eagle-import") (part "R-US_0207/10"))
    )
    (comp (ref "R12")
      (value "470")
      (footprint "eagle-import:0207_10")
      (libsource (lib "eagle-import") (part "R-US_0207/10"))
    )
    (comp (ref "R13")
      (value "150")
      (footprint "eagle-import:0207_10")
      (libsource (lib "eagle-import") (part "R-US_0207/10"))
    )
    (comp (ref "R14")
      (value "470")
      (footprint "eagle-import:0207_10")
      (libsource (lib "eagle-import") (part "R-US_0207/10"))
    )
    (comp (ref "R15")
      (value "150")
      (footprint "eagle-import:0207_10")
      (libsource (lib "eagle-import") (part "R-US_0207/10"))
    )
    (comp (ref "R16")
      (value "470")
      (footprint "eagle-import:0207_10")
      (libsource (lib "eagle-import") (part "R-US_0207/10"))
    )
    (comp (ref "R17")
      (value "150")
      (footprint "eagle-import:0207_10")
      (libsource (lib "eagle-import") (part "R-US_0207/10"))
    )
    (comp (ref "R18")
      (value "470")
      (footprint "eagle-import:0207_10")
      (libsource (lib "eagle-import") (part "R-US_0207/10"))
    )
    (comp (ref "R19")
      (value "150")
      (footprint "eagle-import:0207_10")
      (libsource (lib "eagle-import") (part "R-US_0207/10"))
    )
    (comp (ref "R20")
      (value "470")
      (footprint "eagle-import:0207_10")
      (libsource (lib "eagle-import") (part "R-US_0207/10"))
    )
    (comp (ref "R21")
      (value "150")
      (footprint "eagle-import:0207_10")
      (libsource (lib "eagle-import") (part "R-US_0207/10"))
    )
    (comp (ref "R22")
      (value "470")
      (footprint "eagle-import:0207_10")
      (libsource (lib "eagle-import") (part "R-US_0207/10"))
    )
    (comp (ref "R23")
      (value "150")
      (footprint "eagle-import:0207_10")
      (libsource (lib "eagle-import") (part "R-US_0207/10"))
    )
    (comp (ref "R24")
      (value "470")
      (footprint "eagle-import:0207_10")
      (libsource (lib "eagle-import") (part "R-US_0207/10"))
    )
    (comp (ref "R25")
      (value "150")
      (footprint "eagle-import:0207_10")
      (libsource (lib "eagle-import") (part "R-US_0207/10"))
    )
    (comp (ref "R26")
      (value "470")
      (footprint "eagle-import:0207_10")
      (libsource (lib "eagle-import") (part "R-US_0207/10"))
    )
    (comp (ref "R27")
      (value "150")
      (footprint "eagle-import:0207_10")
      (libsource (lib "eagle-import") (part "R-US_0207/10"))
    )
    (comp (ref "R28")
      (value "470")
      (footprint "eagle-import:0207_10")
      (libsource (lib "eagle-import") (part "R-US_0207/10"))
    )
    (comp (ref "R29")
      (value "150")
      (footprint "eagle-import:0207_10")
      (libsource (lib "eagle-import") (part "R-US_0207/10"))
    )
    (comp (ref "R30")
      (value "470")
      (footprint "eagle-import:0207_10")
      (libsource (lib "eagle-import") (part "R-US_0207/10"))
    )
    (comp (ref "R31")
      (value "150")
      (footprint "eagle-import:0207_10")
      (libsource (lib "eagle-import") (part "R-US_0207/10"))
    )
    (comp (ref "R32")
      (value "470")
      (footprint "eagle-import:0207_10")
      (libsource (lib "eagle-import") (part "R-US_0207/10"))
    )
    (comp (ref "R33")
      (value "470")
      (footprint "eagle-import:0207_10")
      (libsource (lib "eagle-import") (part "R-US_0207/10"))
    )
    (comp (ref "R34")
      (value "470")
      (footprint "eagle-import:0207_10")
      (libsource (lib "eagle-import") (part "R-US_0207/10"))
    )
    (comp (ref "R35")
      (value "470")
      (footprint "eagle-import:0207_10")
      (libsource (lib "eagle-import") (part "R-US_0207/10"))
    )
    (comp (ref "R36")
      (value "470")
      (footprint "eagle-import:0207_10")
      (libsource (lib "eagle-import") (part "R-US_0207/10"))
    )
    (comp (ref "R37")
      (value "470")
      (footprint "eagle-import:0207_10")
      (libsource (lib "eagle-import") (part "R-US_0207/10"))
    )
    (comp (ref "R38")
      (value "470")
      (footprint "eagle-import:0207_10")
      (libsource (lib "eagle-import") (part "R-US_0207/10"))
    )
    (comp (ref "R39")
      (value "470")
      (footprint "eagle-import:0207_10")
      (libsource (lib "eagle-import") (part "R-US_0207/10"))
    )
    (comp (ref "R40")
      (value "470")
      (footprint "eagle-import:0207_10")
      (libsource (lib "eagle-import") (part "R-US_0207/10"))
    )
    (comp (ref "R41")
      (value "470")
      (footprint "eagle-import:0207_10")
      (libsource (lib "eagle-import") (part "R-US_0207/10"))
    )
    (comp (ref "R42")
      (value "470")
      (footprint "eagle-import:0207_10")
      (libsource (lib "eagle-import") (part "R-US_0207/10"))
    )
    (comp (ref "R43")
      (value "470")
      (footprint "eagle-import:0207_10")
      (libsource (lib "eagle-import") (part "R-US_0207/10"))
    )
    (comp (ref "R44")
      (value "470")
      (footprint "eagle-import:0207_10")
      (libsource (lib "eagle-import") (part "R-US_0207/10"))
    )
    (comp (ref "R45")
      (value "470")
      (footprint "eagle-import:0207_10")
      (libsource (lib "eagle-import") (part "R-US_0207/10"))
    )
    (comp (ref "R46")
      (value "470")
      (footprint "eagle-import:0207_10")
      (libsource (lib "eagle-import") (part "R-US_0207/10"))
    )
    (comp (ref "R47")
      (value "470")
      (footprint "eagle-import:0207_10")
      (libsource (lib "eagle-import") (part "R-US_0207/10"))
    )
    (comp (ref "R48")
      (value "470")
      (footprint "eagle-import:0207_10")
      (libsource (lib "eagle-import") (part "R-US_0207/10"))
    )
    (comp (ref "R49")
      (value "470")
      (footprint "eagle-import:0207_10")
      (libsource (lib "eagle-import") (part "R-US_0207/10"))
    )
    (comp (ref "R50")
      (value "470")
      (footprint "eagle-import:0207_10")
      (libsource (lib "eagle-import") (part "R-US_0207/10"))
    )
    (comp (ref "R51")
      (value "470")
      (footprint "eagle-import:0207_10")
      (libsource (lib "eagle-import") (part "R-US_0207/10"))
    )
    (comp (ref "R52")
      (value "470")
      (footprint "eagle-import:0207_10")
      (libsource (lib "eagle-import") (part "R-US_0207/10"))
    )
    (comp (ref "R53")
      (value "1.5K")
      (footprint "eagle-import:0207_10")
      (libsource (lib "eagle-import") (part "R-US_0207/10"))
    )
    (comp (ref "R54")
      (value "150")
      (footprint "eagle-import:0207_10")
      (libsource (lib "eagle-import") (part "R-US_0207/10"))
    )
    (comp (ref "R55")
      (value "open")
      (footprint "eagle-import:0207_10")
      (libsource (lib "eagle-import") (part "R-US_0207/10"))
    )
    (comp (ref "R56")
      (value "470")
      (footprint "eagle-import:0207_10")
      (libsource (lib "eagle-import") (part "R-US_0207/10"))
    )
    (comp (ref "R57")
      (value "1K")
      (footprint "eagle-import:0207_10")
      (libsource (lib "eagle-import") (part "R-US_0207/10"))
    )
    (comp (ref "R58")
      (value "1K")
      (footprint "eagle-import:0207_10")
      (libsource (lib "eagle-import") (part "R-US_0207/10"))
    )
    (comp (ref "R59")
      (value "1K")
      (footprint "eagle-import:0207_10")
      (libsource (lib "eagle-import") (part "R-US_0207/10"))
    )
    (comp (ref "R60")
      (value "1K")
      (footprint "eagle-import:0207_10")
      (libsource (lib "eagle-import") (part "R-US_0207/10"))
    )
    (comp (ref "R61")
      (value "1K")
      (footprint "eagle-import:0207_10")
      (libsource (lib "eagle-import") (part "R-US_0207/10"))
    )
    (comp (ref "R62")
      (value "1K")
      (footprint "eagle-import:0207_10")
      (libsource (lib "eagle-import") (part "R-US_0207/10"))
    )
    (comp (ref "R63")
      (value "1K")
      (footprint "eagle-import:0207_10")
      (libsource (lib "eagle-import") (part "R-US_0207/10"))
    )
    (comp (ref "R64")
      (value "1K")
      (footprint "eagle-import:0207_10")
      (libsource (lib "eagle-import") (part "R-US_0207/10"))
    )
    (comp (ref "R65")
      (value "1K")
      (footprint "eagle-import:0207_10")
      (libsource (lib "eagle-import") (part "R-US_0207/10"))
    )
    (comp (ref "R66")
      (value "1K")
      (footprint "eagle-import:0207_10")
      (libsource (lib "eagle-import") (part "R-US_0207/10"))
    )
    (comp (ref "R67")
      (value "1K")
      (footprint "eagle-import:0207_10")
      (libsource (lib "eagle-import") (part "R-US_0207/10"))
    )
    (comp (ref "R68")
      (value "1K")
      (footprint "eagle-import:0207_10")
      (libsource (lib "eagle-import") (part "R-US_0207/10"))
    )
    (comp (ref "R69")
      (value "1.5K")
      (footprint "eagle-import:0207_10")
      (libsource (lib "eagle-import") (part "R-US_0207/10"))
    )
    (comp (ref "R70")
      (value "1.5K")
      (footprint "eagle-import:0207_10")
      (libsource (lib "eagle-import") (part "R-US_0207/10"))
    )
    (comp (ref "R71")
      (value "1.2K 1/2W")
      (footprint "eagle-import:0411_15")
      (libsource (lib "eagle-import") (part "R-US_0411/15"))
    )
    (comp (ref "R72")
      (value "1.2K 1/2W")
      (footprint "eagle-import:0411_15")
      (libsource (lib "eagle-import") (part "R-US_0411/15"))
    )
    (comp (ref "R73")
      (value "1.2K 1/2W")
      (footprint "eagle-import:0411_15")
      (libsource (lib "eagle-import") (part "R-US_0411/15"))
    )
    (comp (ref "R74")
      (value "470")
      (footprint "eagle-import:0207_10")
      (libsource (lib "eagle-import") (part "R-US_0207/10"))
    )
    (comp (ref "R75")
      (value "1.5K")
      (footprint "eagle-import:0207_10")
      (libsource (lib "eagle-import") (part "R-US_0207/10"))
    )
    (comp (ref "R76")
      (value "1.5K")
      (footprint "eagle-import:0207_10")
      (libsource (lib "eagle-import") (part "R-US_0207/10"))
    )
    (comp (ref "R77")
      (value "1.5K")
      (footprint "eagle-import:0207_10")
      (libsource (lib "eagle-import") (part "R-US_0207/10"))
    )
    (comp (ref "R78")
      (value "1.5K")
      (footprint "eagle-import:0207_10")
      (libsource (lib "eagle-import") (part "R-US_0207/10"))
    )
    (comp (ref "R79")
      (value "1.5K")
      (footprint "eagle-import:0207_10")
      (libsource (lib "eagle-import") (part "R-US_0207/10"))
    )
    (comp (ref "R80")
      (value "1.5K")
      (footprint "eagle-import:0207_10")
      (libsource (lib "eagle-import") (part "R-US_0207/10"))
    )
    (comp (ref "R81")
      (value "1.5K")
      (footprint "eagle-import:0207_10")
      (libsource (lib "eagle-import") (part "R-US_0207/10"))
    )
    (comp (ref "R82")
      (value "1.5K")
      (footprint "eagle-import:0207_10")
      (libsource (lib "eagle-import") (part "R-US_0207/10"))
    )
    (comp (ref "R83")
      (value "1.5K")
      (footprint "eagle-import:0207_10")
      (libsource (lib "eagle-import") (part "R-US_0207/10"))
    )
    (comp (ref "R84")
      (value "1.5K")
      (footprint "eagle-import:0207_10")
      (libsource (lib "eagle-import") (part "R-US_0207/10"))
    )
    (comp (ref "R85")
      (value "1.5K")
      (footprint "eagle-import:0207_10")
      (libsource (lib "eagle-import") (part "R-US_0207/10"))
    )
    (comp (ref "R86")
      (value "1.5K")
      (footprint "eagle-import:0207_10")
      (libsource (lib "eagle-import") (part "R-US_0207/10"))
    )
    (comp (ref "R87")
      (value "1.5K")
      (footprint "eagle-import:0207_10")
      (libsource (lib "eagle-import") (part "R-US_0207/10"))
    )
    (comp (ref "R88")
      (value "1.5K")
      (footprint "eagle-import:0207_10")
      (libsource (lib "eagle-import") (part "R-US_0207/10"))
    )
    (comp (ref "R89")
      (value "1.5K")
      (footprint "eagle-import:0207_10")
      (libsource (lib "eagle-import") (part "R-US_0207/10"))
    )
    (comp (ref "R90")
      (value "1.5K")
      (footprint "eagle-import:0207_10")
      (libsource (lib "eagle-import") (part "R-US_0207/10"))
    )
    (comp (ref "R91")
      (value "1.5K")
      (footprint "eagle-import:0207_10")
      (libsource (lib "eagle-import") (part "R-US_0207/10"))
    )
    (comp (ref "R92")
      (value "1.5K")
      (footprint "eagle-import:0207_10")
      (libsource (lib "eagle-import") (part "R-US_0207/10"))
    )
    (comp (ref "R93")
      (value "1.5K")
      (footprint "eagle-import:0207_10")
      (libsource (lib "eagle-import") (part "R-US_0207/10"))
    )
    (comp (ref "R94")
      (value "1.5K")
      (footprint "eagle-import:0207_10")
      (libsource (lib "eagle-import") (part "R-US_0207/10"))
    )
    (comp (ref "R95")
      (value "1.5K")
      (footprint "eagle-import:0207_10")
      (libsource (lib "eagle-import") (part "R-US_0207/10"))
    )
    (comp (ref "R96")
      (value "1.5K")
      (footprint "eagle-import:0207_10")
      (libsource (lib "eagle-import") (part "R-US_0207/10"))
    )
    (comp (ref "R97")
      (value "1.5K")
      (footprint "eagle-import:0207_10")
      (libsource (lib "eagle-import") (part "R-US_0207/10"))
    )
    (comp (ref "R98")
      (value "1.5K")
      (footprint "eagle-import:0207_10")
      (libsource (lib "eagle-import") (part "R-US_0207/10"))
    )
    (comp (ref "R99")
      (value "1.5K")
      (footprint "eagle-import:0207_10")
      (libsource (lib "eagle-import") (part "R-US_0207/10"))
    )
    (comp (ref "R100")
      (value "1.5K")
      (footprint "eagle-import:0207_10")
      (libsource (lib "eagle-import") (part "R-US_0207/10"))
    )
    (comp (ref "R101")
      (value "1.5K")
      (footprint "eagle-import:0207_10")
      (libsource (lib "eagle-import") (part "R-US_0207/10"))
    )
    (comp (ref "R102")
      (value "1.5K")
      (footprint "eagle-import:0207_10")
      (libsource (lib "eagle-import") (part "R-US_0207/10"))
    )
    (comp (ref "R103")
      (value "1.5K")
      (footprint "eagle-import:0207_10")
      (libsource (lib "eagle-import") (part "R-US_0207/10"))
    )
    (comp (ref "R104")
      (value "1.5K")
      (footprint "eagle-import:0207_10")
      (libsource (lib "eagle-import") (part "R-US_0207/10"))
    )
    (comp (ref "R105")
      (value "1.5K")
      (footprint "eagle-import:0207_10")
      (libsource (lib "eagle-import") (part "R-US_0207/10"))
    )
    (comp (ref "R106")
      (value "1.5K")
      (footprint "eagle-import:0207_10")
      (libsource (lib "eagle-import") (part "R-US_0207/10"))
    )
    (comp (ref "R107")
      (value "1.5K")
      (footprint "eagle-import:0207_10")
      (libsource (lib "eagle-import") (part "R-US_0207/10"))
    )
    (comp (ref "R108")
      (value "1.5K")
      (footprint "eagle-import:0207_10")
      (libsource (lib "eagle-import") (part "R-US_0207/10"))
    )
    (comp (ref "R109")
      (value "1.5K")
      (footprint "eagle-import:0207_10")
      (libsource (lib "eagle-import") (part "R-US_0207/10"))
    )
    (comp (ref "R110")
      (value "1.5K")
      (footprint "eagle-import:0207_10")
      (libsource (lib "eagle-import") (part "R-US_0207/10"))
    )
    (comp (ref "R111")
      (value "1.5K")
      (footprint "eagle-import:0207_10")
      (libsource (lib "eagle-import") (part "R-US_0207/10"))
    )
    (comp (ref "R112")
      (value "1.5K")
      (footprint "eagle-import:0207_10")
      (libsource (lib "eagle-import") (part "R-US_0207/10"))
    )
    (comp (ref "R113")
      (value "1.5K")
      (footprint "eagle-import:0207_10")
      (libsource (lib "eagle-import") (part "R-US_0207/10"))
    )
    (comp (ref "R114")
      (value "1.5K")
      (footprint "eagle-import:0207_10")
      (libsource (lib "eagle-import") (part "R-US_0207/10"))
    )
    (comp (ref "R115")
      (value "1.5K")
      (footprint "eagle-import:0207_10")
      (libsource (lib "eagle-import") (part "R-US_0207/10"))
    )
    (comp (ref "R116")
      (value "1.5K")
      (footprint "eagle-import:0207_10")
      (libsource (lib "eagle-import") (part "R-US_0207/10"))
    )
    (comp (ref "R117")
      (value "1.5K")
      (footprint "eagle-import:0207_10")
      (libsource (lib "eagle-import") (part "R-US_0207/10"))
    )
    (comp (ref "R118")
      (value "1.2K 1/2W")
      (footprint "eagle-import:0411_15")
      (libsource (lib "eagle-import") (part "R-US_0411/15"))
    )
    (comp (ref "R119")
      (value "1K 1/2W")
      (footprint "eagle-import:0411_15")
      (libsource (lib "eagle-import") (part "R-US_0411/15"))
    )
    (comp (ref "R120")
      (value "1K 1/2W")
      (footprint "eagle-import:0411_15")
      (libsource (lib "eagle-import") (part "R-US_0411/15"))
    )
    (comp (ref "R121")
      (value "1K 1/2W")
      (footprint "eagle-import:0411_15")
      (libsource (lib "eagle-import") (part "R-US_0411/15"))
    )
    (comp (ref "R122")
      (value "1K 1/2W")
      (footprint "eagle-import:0411_15")
      (libsource (lib "eagle-import") (part "R-US_0411/15"))
    )
    (comp (ref "R123")
      (value "1K 1/2W")
      (footprint "eagle-import:0411_15")
      (libsource (lib "eagle-import") (part "R-US_0411/15"))
    )
    (comp (ref "R124")
      (value "1K 1/2W")
      (footprint "eagle-import:0411_15")
      (libsource (lib "eagle-import") (part "R-US_0411/15"))
    )
    (comp (ref "R125")
      (value "150")
      (footprint "eagle-import:0207_10")
      (libsource (lib "eagle-import") (part "R-US_0207/10"))
    )
    (comp (ref "R126")
      (value "150")
      (footprint "eagle-import:0207_10")
      (libsource (lib "eagle-import") (part "R-US_0207/10"))
    )
    (comp (ref "R127")
      (value "470")
      (footprint "eagle-import:0207_10")
      (libsource (lib "eagle-import") (part "R-US_0207/10"))
    )
    (comp (ref "R128")
      (value "470")
      (footprint "eagle-import:0207_10")
      (libsource (lib "eagle-import") (part "R-US_0207/10"))
    )
    (comp (ref "R129")
      (value "150")
      (footprint "eagle-import:0207_10")
      (libsource (lib "eagle-import") (part "R-US_0207/10"))
    )
    (comp (ref "T1")
      (value "16-09651")
      (footprint "eagle-import:DIL16")
      (libsource (lib "eagle-import") (part "16-09651"))
    )
    (comp (ref "U$1")
      (value "OUTLINE-OMNIBUS")
      (footprint "eagle-import:OMNIBUS")
      (libsource (lib "eagle-import") (part "OUTLINE-OMNIBUS"))
    )
    (comp (ref "U$2")
      (value "QUAD")
      (footprint "eagle-import:EDGE-CON8")
      (libsource (lib "eagle-import") (part "QUAD"))
    )
  )
  (nets
    (net (code "1") (name "+15V") (class "Default")
      (node (ref "C1") (pin "1") (pinfunction "1_1") (pintype "passive"))
      (node (ref "C13") (pin "+") (pinfunction "+_+") (pintype "passive"))
      (node (ref "C2") (pin "+") (pinfunction "+_+") (pintype "passive"))
      (node (ref "C21") (pin "1") (pinfunction "1_1") (pintype "passive"))
      (node (ref "C27") (pin "1") (pinfunction "1_1") (pintype "passive"))
      (node (ref "C28") (pin "1") (pinfunction "1_1") (pintype "passive"))
      (node (ref "C3") (pin "1") (pinfunction "1_1") (pintype "passive"))
      (node (ref "C33") (pin "+") (pinfunction "+_+") (pintype "passive"))
      (node (ref "C5") (pin "1") (pinfunction "1_1") (pintype "passive"))
      (node (ref "C9") (pin "1") (pinfunction "1_1") (pintype "passive"))
      (node (ref "D97") (pin "A") (pinfunction "A_A") (pintype "passive"))
      (node (ref "Q1") (pin "C") (pinfunction "C_C") (pintype "passive"))
      (node (ref "Q2") (pin "C") (pinfunction "C_C") (pintype "passive"))
      (node (ref "Q3") (pin "C") (pinfunction "C_C") (pintype "passive"))
      (node (ref "R100") (pin "2") (pinfunction "2_2") (pintype "passive"))
      (node (ref "R101") (pin "2") (pinfunction "2_2") (pintype "passive"))
      (node (ref "R102") (pin "2") (pinfunction "2_2") (pintype "passive"))
      (node (ref "R103") (pin "2") (pinfunction "2_2") (pintype "passive"))
      (node (ref "R104") (pin "2") (pinfunction "2_2") (pintype "passive"))
      (node (ref "R105") (pin "2") (pinfunction "2_2") (pintype "passive"))
      (node (ref "R106") (pin "2") (pinfunction "2_2") (pintype "passive"))
      (node (ref "R107") (pin "2") (pinfunction "2_2") (pintype "passive"))
      (node (ref "R108") (pin "2") (pinfunction "2_2") (pintype "passive"))
      (node (ref "R109") (pin "2") (pinfunction "2_2") (pintype "passive"))
      (node (ref "R110") (pin "2") (pinfunction "2_2") (pintype "passive"))
      (node (ref "R111") (pin "2") (pinfunction "2_2") (pintype "passive"))
      (node (ref "R112") (pin "2") (pinfunction "2_2") (pintype "passive"))
      (node (ref "R113") (pin "2") (pinfunction "2_2") (pintype "passive"))
      (node (ref "R114") (pin "2") (pinfunction "2_2") (pintype "passive"))
      (node (ref "R115") (pin "2") (pinfunction "2_2") (pintype "passive"))
      (node (ref "R116") (pin "2") (pinfunction "2_2") (pintype "passive"))
      (node (ref "R117") (pin "2") (pinfunction "2_2") (pintype "passive"))
      (node (ref "R53") (pin "2") (pinfunction "2_2") (pintype "passive"))
      (node (ref "R70") (pin "2") (pinfunction "2_2") (pintype "passive"))
      (node (ref "R75") (pin "2") (pinfunction "2_2") (pintype "passive"))
      (node (ref "R76") (pin "2") (pinfunction "2_2") (pintype "passive"))
      (node (ref "R77") (pin "2") (pinfunction "2_2") (pintype "passive"))
      (node (ref "R78") (pin "2") (pinfunction "2_2") (pintype "passive"))
      (node (ref "R79") (pin "2") (pinfunction "2_2") (pintype "passive"))
      (node (ref "R80") (pin "2") (pinfunction "2_2") (pintype "passive"))
      (node (ref "R81") (pin "2") (pinfunction "2_2") (pintype "passive"))
      (node (ref "R82") (pin "2") (pinfunction "2_2") (pintype "passive"))
      (node (ref "R83") (pin "2") (pinfunction "2_2") (pintype "passive"))
      (node (ref "R84") (pin "2") (pinfunction "2_2") (pintype "passive"))
      (node (ref "R85") (pin "2") (pinfunction "2_2") (pintype "passive"))
      (node (ref "R86") (pin "2") (pinfunction "2_2") (pintype "passive"))
      (node (ref "R87") (pin "2") (pinfunction "2_2") (pintype "passive"))
      (node (ref "R88") (pin "2") (pinfunction "2_2") (pintype "passive"))
      (node (ref "R89") (pin "2") (pinfunction "2_2") (pintype "passive"))
      (node (ref "R90") (pin "2") (pinfunction "2_2") (pintype "passive"))
      (node (ref "R91") (pin "2") (pinfunction "2_2") (pintype "passive"))
      (node (ref "R92") (pin "2") (pinfunction "2_2") (pintype "passive"))
      (node (ref "R93") (pin "2") (pinfunction "2_2") (pintype "passive"))
      (node (ref "R94") (pin "2") (pinfunction "2_2") (pintype "passive"))
      (node (ref "R95") (pin "2") (pinfunction "2_2") (pintype "passive"))
      (node (ref "R96") (pin "2") (pinfunction "2_2") (pintype "passive"))
      (node (ref "R97") (pin "2") (pinfunction "2_2") (pintype "passive"))
      (node (ref "R98") (pin "2") (pinfunction "2_2") (pintype "passive"))
      (node (ref "R99") (pin "2") (pinfunction "2_2") (pintype "passive"))
      (node (ref "U$2") (pin "DA2") (pinfunction "1_DA2") (pintype "bidirectional"))
    )
    (net (code "2") (name "-15V") (class "Default")
      (node (ref "C14") (pin "2") (pinfunction "2_2") (pintype "passive"))
      (node (ref "R118") (pin "1") (pinfunction "1_1") (pintype "passive"))
      (node (ref "R119") (pin "1") (pinfunction "1_1") (pintype "passive"))
      (node (ref "R120") (pin "1") (pinfunction "1_1") (pintype "passive"))
      (node (ref "R121") (pin "1") (pinfunction "1_1") (pintype "passive"))
      (node (ref "R122") (pin "1") (pinfunction "1_1") (pintype "passive"))
      (node (ref "R123") (pin "1") (pinfunction "1_1") (pintype "passive"))
      (node (ref "R124") (pin "1") (pinfunction "1_1") (pintype "passive"))
      (node (ref "R71") (pin "1") (pinfunction "1_1") (pintype "passive"))
      (node (ref "R72") (pin "1") (pinfunction "1_1") (pintype "passive"))
      (node (ref "R73") (pin "1") (pinfunction "1_1") (pintype "passive"))
      (node (ref "U$2") (pin "CB2") (pinfunction "1_CB2") (pintype "bidirectional"))
      (node (ref "U$2") (pin "DB2") (pinfunction "1_DB2") (pintype "bidirectional"))
    )
    (net (code "3") (name "/+3V0") (class "Default")
      (node (ref "E1") (pin "10") (pinfunction "I1_10") (pintype "input"))
      (node (ref "E1") (pin "12") (pinfunction "I0_12") (pintype "input"))
      (node (ref "E1") (pin "3") (pinfunction "O_3") (pintype "output"))
      (node (ref "E1") (pin "4") (pinfunction "I0_4") (pintype "input"))
    )
    (net (code "4") (name "/INHIBIT") (class "Default")
      (node (ref "D13") (pin "C") (pinfunction "C_C") (pintype "passive"))
      (node (ref "R25") (pin "1") (pinfunction "1_1") (pintype "passive"))
      (node (ref "R26") (pin "2") (pinfunction "2_2") (pintype "passive"))
      (node (ref "U$2") (pin "AP2") (pinfunction "1_AP2") (pintype "bidirectional"))
    )
    (net (code "5") (name "/INITIALIZE") (class "Default")
      (node (ref "D190") (pin "C") (pinfunction "C_C") (pintype "passive"))
      (node (ref "R121") (pin "2") (pinfunction "2_2") (pintype "passive"))
      (node (ref "R122") (pin "2") (pinfunction "2_2") (pintype "passive"))
      (node (ref "U$2") (pin "CR1") (pinfunction "1_CR1") (pintype "bidirectional"))
    )
    (net (code "6") (name "/INT_IN_PROG") (class "Default")
      (node (ref "D94") (pin "C") (pinfunction "C_C") (pintype "passive"))
      (node (ref "D95") (pin "A") (pinfunction "A_A") (pintype "passive"))
      (node (ref "R69") (pin "1") (pinfunction "1_1") (pintype "passive"))
      (node (ref "U$2") (pin "BP2") (pinfunction "1_BP2") (pintype "bidirectional"))
    )
    (net (code "7") (name "/INT_STROBE") (class "Default")
      (node (ref "D14") (pin "C") (pinfunction "C_C") (pintype "passive"))
      (node (ref "E1") (pin "13") (pinfunction "I1_13") (pintype "input"))
      (node (ref "R27") (pin "1") (pinfunction "1_1") (pintype "passive"))
      (node (ref "R28") (pin "2") (pinfunction "2_2") (pintype "passive"))
      (node (ref "U$2") (pin "BD2") (pinfunction "1_BD2") (pintype "bidirectional"))
    )
    (net (code "8") (name "/POWER_OK") (class "Default")
      (node (ref "D189") (pin "C") (pinfunction "C_C") (pintype "passive"))
      (node (ref "D193") (pin "C") (pinfunction "C_C") (pintype "passive"))
      (node (ref "R119") (pin "2") (pinfunction "2_2") (pintype "passive"))
      (node (ref "R120") (pin "2") (pinfunction "2_2") (pintype "passive"))
      (node (ref "U$2") (pin "BV2") (pinfunction "1_BV2") (pintype "bidirectional"))
    )
    (net (code "9") (name "/PULSE_LA") (class "Default")
      (node (ref "D191") (pin "C") (pinfunction "C_C") (pintype "passive"))
      (node (ref "R123") (pin "2") (pinfunction "2_2") (pintype "passive"))
      (node (ref "R124") (pin "2") (pinfunction "2_2") (pintype "passive"))
      (node (ref "U$2") (pin "DR2") (pinfunction "1_DR2") (pintype "bidirectional"))
    )
    (net (code "10") (name "/RES1") (class "Default")
      (node (ref "D131") (pin "C") (pinfunction "C_C") (pintype "passive"))
      (node (ref "D132") (pin "A") (pinfunction "A_A") (pintype "passive"))
      (node (ref "R91") (pin "1") (pinfunction "1_1") (pintype "passive"))
      (node (ref "U$2") (pin "BR2") (pinfunction "1_BR2") (pintype "bidirectional"))
    )
    (net (code "11") (name "/RES2") (class "Default")
      (node (ref "D133") (pin "C") (pinfunction "C_C") (pintype "passive"))
      (node (ref "D134") (pin "A") (pinfunction "A_A") (pintype "passive"))
      (node (ref "R92") (pin "1") (pinfunction "1_1") (pintype "passive"))
      (node (ref "U$2") (pin "BS2") (pinfunction "1_BS2") (pintype "bidirectional"))
    )
    (net (code "12") (name "/RETURN") (class "Default")
      (node (ref "D9") (pin "C") (pinfunction "C_C") (pintype "passive"))
      (node (ref "R17") (pin "1") (pinfunction "1_1") (pintype "passive"))
      (node (ref "R18") (pin "2") (pinfunction "2_2") (pintype "passive"))
      (node (ref "U$2") (pin "AR2") (pinfunction "1_AR2") (pintype "bidirectional"))
    )
    (net (code "13") (name "/SOURCE") (class "Default")
      (node (ref "D10") (pin "C") (pinfunction "C_C") (pintype "passive"))
      (node (ref "R19") (pin "1") (pinfunction "1_1") (pintype "passive"))
      (node (ref "R20") (pin "2") (pinfunction "2_2") (pintype "passive"))
      (node (ref "U$2") (pin "AL2") (pinfunction "1_AL2") (pintype "bidirectional"))
    )
    (net (code "14") (name "/STROBE") (class "Default")
      (node (ref "D11") (pin "C") (pinfunction "C_C") (pintype "passive"))
      (node (ref "R21") (pin "1") (pinfunction "1_1") (pintype "passive"))
      (node (ref "R22") (pin "2") (pinfunction "2_2") (pintype "passive"))
      (node (ref "U$2") (pin "AM2") (pinfunction "1_AM2") (pintype "bidirectional"))
    )
    (net (code "15") (name "/TP1") (class "Default")
      (node (ref "D2") (pin "C") (pinfunction "C_C") (pintype "passive"))
      (node (ref "R3") (pin "1") (pinfunction "1_1") (pintype "passive"))
      (node (ref "R4") (pin "2") (pinfunction "2_2") (pintype "passive"))
      (node (ref "U$2") (pin "CD2") (pinfunction "1_CD2") (pintype "bidirectional"))
    )
    (net (code "16") (name "/TP2") (class "Default")
      (node (ref "D3") (pin "C") (pinfunction "C_C") (pintype "passive"))
      (node (ref "E1") (pin "9") (pinfunction "I0_9") (pintype "input"))
      (node (ref "R5") (pin "1") (pinfunction "1_1") (pintype "passive"))
      (node (ref "R6") (pin "2") (pinfunction "2_2") (pintype "passive"))
      (node (ref "U$2") (pin "CE2") (pinfunction "1_CE2") (pintype "bidirectional"))
    )
    (net (code "17") (name "/TP3") (class "Default")
      (node (ref "D4") (pin "C") (pinfunction "C_C") (pintype "passive"))
      (node (ref "R7") (pin "1") (pinfunction "1_1") (pintype "passive"))
      (node (ref "R8") (pin "2") (pinfunction "2_2") (pintype "passive"))
      (node (ref "U$2") (pin "CH2") (pinfunction "1_CH2") (pintype "bidirectional"))
    )
    (net (code "18") (name "/TP4") (class "Default")
      (node (ref "D1") (pin "C") (pinfunction "C_C") (pintype "passive"))
      (node (ref "E1") (pin "5") (pinfunction "I1_5") (pintype "input"))
      (node (ref "R1") (pin "1") (pinfunction "1_1") (pintype "passive"))
      (node (ref "R2") (pin "2") (pinfunction "2_2") (pintype "passive"))
      (node (ref "U$2") (pin "CJ2") (pinfunction "1_CJ2") (pintype "bidirectional"))
    )
    (net (code "19") (name "/WRITE") (class "Default")
      (node (ref "D12") (pin "C") (pinfunction "C_C") (pintype "passive"))
      (node (ref "R23") (pin "1") (pinfunction "1_1") (pintype "passive"))
      (node (ref "R24") (pin "2") (pinfunction "2_2") (pintype "passive"))
      (node (ref "U$2") (pin "AS2") (pinfunction "1_AS2") (pintype "bidirectional"))
    )
    (net (code "20") (name "/~{BRK_CYCLE}") (class "Default")
      (node (ref "D129") (pin "C") (pinfunction "C_C") (pintype "passive"))
      (node (ref "D130") (pin "A") (pinfunction "A_A") (pintype "passive"))
      (node (ref "R90") (pin "1") (pinfunction "1_1") (pintype "passive"))
      (node (ref "U$2") (pin "BL2") (pinfunction "1_BL2") (pintype "bidirectional"))
    )
    (net (code "21") (name "/~{BRK_D_CTL}") (class "Default")
      (node (ref "D127") (pin "C") (pinfunction "C_C") (pintype "passive"))
      (node (ref "D128") (pin "A") (pinfunction "A_A") (pintype "passive"))
      (node (ref "R89") (pin "1") (pinfunction "1_1") (pintype "passive"))
      (node (ref "U$2") (pin "BK2") (pinfunction "1_BK2") (pintype "bidirectional"))
    )
    (net (code "22") (name "/~{BRK_IN_PROG}") (class "Default")
      (node (ref "D111") (pin "C") (pinfunction "C_C") (pintype "passive"))
      (node (ref "D112") (pin "A") (pinfunction "A_A") (pintype "passive"))
      (node (ref "R81") (pin "1") (pinfunction "1_1") (pintype "passive"))
      (node (ref "U$2") (pin "BE2") (pinfunction "1_BE2") (pintype "bidirectional"))
    )
    (net (code "23") (name "/~{BUS_STROBE}") (class "Default")
      (node (ref "D194") (pin "C") (pinfunction "C_C") (pintype "passive"))
      (node (ref "R126") (pin "1") (pinfunction "1_1") (pintype "passive"))
      (node (ref "R128") (pin "2") (pinfunction "2_2") (pintype "passive"))
      (node (ref "U$2") (pin "CK1") (pinfunction "1_CK1") (pintype "bidirectional"))
    )
    (net (code "24") (name "/~{C0}") (class "Default")
      (node (ref "D135") (pin "C") (pinfunction "C_C") (pintype "passive"))
      (node (ref "D136") (pin "A") (pinfunction "A_A") (pintype "passive"))
      (node (ref "R93") (pin "1") (pinfunction "1_1") (pintype "passive"))
      (node (ref "U$2") (pin "CE1") (pinfunction "1_CE1") (pintype "bidirectional"))
    )
    (net (code "25") (name "/~{C1}") (class "Default")
      (node (ref "D137") (pin "C") (pinfunction "C_C") (pintype "passive"))
      (node (ref "D138") (pin "A") (pinfunction "A_A") (pintype "passive"))
      (node (ref "R94") (pin "1") (pinfunction "1_1") (pintype "passive"))
      (node (ref "U$2") (pin "CH1") (pinfunction "1_CH1") (pintype "bidirectional"))
    )
    (net (code "26") (name "/~{C2}") (class "Default")
      (node (ref "D139") (pin "C") (pinfunction "C_C") (pintype "passive"))
      (node (ref "D140") (pin "A") (pinfunction "A_A") (pintype "passive"))
      (node (ref "R95") (pin "1") (pinfunction "1_1") (pintype "passive"))
      (node (ref "U$2") (pin "CJ1") (pinfunction "1_CJ1") (pintype "bidirectional"))
    )
    (net (code "27") (name "/~{CPMA_DISABL}") (class "Default")
      (node (ref "D173") (pin "C") (pinfunction "C_C") (pintype "passive"))
      (node (ref "D174") (pin "A") (pinfunction "A_A") (pintype "passive"))
      (node (ref "R111") (pin "1") (pinfunction "1_1") (pintype "passive"))
      (node (ref "U$2") (pin "CU1") (pinfunction "1_CU1") (pintype "bidirectional"))
    )
    (net (code "28") (name "/~{DATA0}") (class "Default")
      (node (ref "D70") (pin "C") (pinfunction "C_C") (pintype "passive"))
      (node (ref "D71") (pin "A") (pinfunction "A_A") (pintype "passive"))
      (node (ref "R57") (pin "1") (pinfunction "1_1") (pintype "passive"))
      (node (ref "U$2") (pin "AR1") (pinfunction "1_AR1") (pintype "bidirectional"))
    )
    (net (code "29") (name "/~{DATA1}") (class "Default")
      (node (ref "D72") (pin "C") (pinfunction "C_C") (pintype "passive"))
      (node (ref "D73") (pin "A") (pinfunction "A_A") (pintype "passive"))
      (node (ref "R58") (pin "1") (pinfunction "1_1") (pintype "passive"))
      (node (ref "U$2") (pin "AS1") (pinfunction "1_AS1") (pintype "bidirectional"))
    )
    (net (code "30") (name "/~{DATA2}") (class "Default")
      (node (ref "D74") (pin "C") (pinfunction "C_C") (pintype "passive"))
      (node (ref "D75") (pin "A") (pinfunction "A_A") (pintype "passive"))
      (node (ref "R59") (pin "1") (pinfunction "1_1") (pintype "passive"))
      (node (ref "U$2") (pin "AU1") (pinfunction "1_AU1") (pintype "bidirectional"))
    )
    (net (code "31") (name "/~{DATA3}") (class "Default")
      (node (ref "D76") (pin "C") (pinfunction "C_C") (pintype "passive"))
      (node (ref "D77") (pin "A") (pinfunction "A_A") (pintype "passive"))
      (node (ref "R60") (pin "1") (pinfunction "1_1") (pintype "passive"))
      (node (ref "U$2") (pin "AV1") (pinfunction "1_AV1") (pintype "bidirectional"))
    )
    (net (code "32") (name "/~{DATA4}") (class "Default")
      (node (ref "D78") (pin "C") (pinfunction "C_C") (pintype "passive"))
      (node (ref "D79") (pin "A") (pinfunction "A_A") (pintype "passive"))
      (node (ref "R61") (pin "1") (pinfunction "1_1") (pintype "passive"))
      (node (ref "U$2") (pin "BR1") (pinfunction "1_BR1") (pintype "bidirectional"))
    )
    (net (code "33") (name "/~{DATA5}") (class "Default")
      (node (ref "D80") (pin "C") (pinfunction "C_C") (pintype "passive"))
      (node (ref "D81") (pin "A") (pinfunction "A_A") (pintype "passive"))
      (node (ref "R62") (pin "1") (pinfunction "1_1") (pintype "passive"))
      (node (ref "U$2") (pin "BS1") (pinfunction "1_BS1") (pintype "bidirectional"))
    )
    (net (code "34") (name "/~{DATA6}") (class "Default")
      (node (ref "D82") (pin "C") (pinfunction "C_C") (pintype "passive"))
      (node (ref "D83") (pin "A") (pinfunction "A_A") (pintype "passive"))
      (node (ref "R63") (pin "1") (pinfunction "1_1") (pintype "passive"))
      (node (ref "U$2") (pin "BU1") (pinfunction "1_BU1") (pintype "bidirectional"))
    )
    (net (code "35") (name "/~{DATA7}") (class "Default")
      (node (ref "D84") (pin "C") (pinfunction "C_C") (pintype "passive"))
      (node (ref "D85") (pin "A") (pinfunction "A_A") (pintype "passive"))
      (node (ref "R64") (pin "1") (pinfunction "1_1") (pintype "passive"))
      (node (ref "U$2") (pin "BV1") (pinfunction "1_BV1") (pintype "bidirectional"))
    )
    (net (code "36") (name "/~{DATA8}") (class "Default")
      (node (ref "D86") (pin "C") (pinfunction "C_C") (pintype "passive"))
      (node (ref "D87") (pin "A") (pinfunction "A_A") (pintype "passive"))
      (node (ref "R65") (pin "1") (pinfunction "1_1") (pintype "passive"))
      (node (ref "U$2") (pin "DR1") (pinfunction "1_DR1") (pintype "bidirectional"))
    )
    (net (code "37") (name "/~{DATA9}") (class "Default")
      (node (ref "D88") (pin "C") (pinfunction "C_C") (pintype "passive"))
      (node (ref "D89") (pin "A") (pinfunction "A_A") (pintype "passive"))
      (node (ref "R66") (pin "1") (pinfunction "1_1") (pintype "passive"))
      (node (ref "U$2") (pin "DS1") (pinfunction "1_DS1") (pintype "bidirectional"))
    )
    (net (code "38") (name "/~{DATA10}") (class "Default")
      (node (ref "D90") (pin "C") (pinfunction "C_C") (pintype "passive"))
      (node (ref "D91") (pin "A") (pinfunction "A_A") (pintype "passive"))
      (node (ref "R67") (pin "1") (pinfunction "1_1") (pintype "passive"))
      (node (ref "U$2") (pin "DU1") (pinfunction "1_DU1") (pintype "bidirectional"))
    )
    (net (code "39") (name "/~{DATA11}") (class "Default")
      (node (ref "D92") (pin "C") (pinfunction "C_C") (pintype "passive"))
      (node (ref "D93") (pin "A") (pinfunction "A_A") (pintype "passive"))
      (node (ref "R68") (pin "1") (pinfunction "1_1") (pintype "passive"))
      (node (ref "U$2") (pin "DV1") (pinfunction "1_DV1") (pintype "bidirectional"))
    )
    (net (code "40") (name "/~{D}") (class "Default")
      (node (ref "D54") (pin "C") (pinfunction "C_C") (pintype "passive"))
      (node (ref "D55") (pin "A") (pinfunction "A_A") (pintype "passive"))
      (node (ref "R51") (pin "1") (pinfunction "1_1") (pintype "passive"))
      (node (ref "U$2") (pin "DK2") (pinfunction "1_DK2") (pintype "bidirectional"))
    )
    (net (code "41") (name "/~{EMA0}") (class "Default")
      (node (ref "D26") (pin "C") (pinfunction "C_C") (pintype "passive"))
      (node (ref "D27") (pin "A") (pinfunction "A_A") (pintype "passive"))
      (node (ref "R37") (pin "1") (pinfunction "1_1") (pintype "passive"))
      (node (ref "U$2") (pin "AD2") (pinfunction "1_AD2") (pintype "bidirectional"))
    )
    (net (code "42") (name "/~{EMA1}") (class "Default")
      (node (ref "D28") (pin "C") (pinfunction "C_C") (pintype "passive"))
      (node (ref "D29") (pin "A") (pinfunction "A_A") (pintype "passive"))
      (node (ref "R38") (pin "1") (pinfunction "1_1") (pintype "passive"))
      (node (ref "U$2") (pin "AE2") (pinfunction "1_AE2") (pintype "bidirectional"))
    )
    (net (code "43") (name "/~{EMA2}") (class "Default")
      (node (ref "D30") (pin "C") (pinfunction "C_C") (pintype "passive"))
      (node (ref "D31") (pin "A") (pinfunction "A_A") (pintype "passive"))
      (node (ref "R39") (pin "1") (pinfunction "1_1") (pintype "passive"))
      (node (ref "U$2") (pin "AH2") (pinfunction "1_AH2") (pintype "bidirectional"))
    )
    (net (code "44") (name "/~{E}") (class "Default")
      (node (ref "D56") (pin "C") (pinfunction "C_C") (pintype "passive"))
      (node (ref "D57") (pin "A") (pinfunction "A_A") (pintype "passive"))
      (node (ref "R52") (pin "1") (pinfunction "1_1") (pintype "passive"))
      (node (ref "U$2") (pin "DL2") (pinfunction "1_DL2") (pintype "bidirectional"))
    )
    (net (code "45") (name "/~{F_SET}") (class "Default")
      (node (ref "D159") (pin "C") (pinfunction "C_C") (pintype "passive"))
      (node (ref "D160") (pin "A") (pinfunction "A_A") (pintype "passive"))
      (node (ref "R104") (pin "1") (pinfunction "1_1") (pintype "passive"))
      (node (ref "U$2") (pin "DP2") (pinfunction "1_DP2") (pintype "bidirectional"))
    )
    (net (code "46") (name "/~{F}") (class "Default")
      (node (ref "D52") (pin "C") (pinfunction "C_C") (pintype "passive"))
      (node (ref "D53") (pin "A") (pinfunction "A_A") (pintype "passive"))
      (node (ref "R50") (pin "1") (pinfunction "1_1") (pintype "passive"))
      (node (ref "U$2") (pin "DJ2") (pinfunction "1_DJ2") (pintype "bidirectional"))
    )
    (net (code "47") (name "/~{IND1}") (class "Default")
      (node (ref "D151") (pin "C") (pinfunction "C_C") (pintype "passive"))
      (node (ref "D152") (pin "A") (pinfunction "A_A") (pintype "passive"))
      (node (ref "R100") (pin "1") (pinfunction "1_1") (pintype "passive"))
      (node (ref "U$2") (pin "CU2") (pinfunction "1_CU2") (pintype "bidirectional"))
    )
    (net (code "48") (name "/~{IND2}") (class "Default")
      (node (ref "D153") (pin "C") (pinfunction "C_C") (pintype "passive"))
      (node (ref "D154") (pin "A") (pinfunction "A_A") (pintype "passive"))
      (node (ref "R101") (pin "1") (pinfunction "1_1") (pintype "passive"))
      (node (ref "U$2") (pin "CV2") (pinfunction "1_CV2") (pintype "bidirectional"))
    )
    (net (code "49") (name "/~{INTERNAL_IO}") (class "Default")
      (node (ref "D155") (pin "C") (pinfunction "C_C") (pintype "passive"))
      (node (ref "D156") (pin "A") (pinfunction "A_A") (pintype "passive"))
      (node (ref "R102") (pin "1") (pinfunction "1_1") (pintype "passive"))
      (node (ref "U$2") (pin "CL1") (pinfunction "1_CL1") (pintype "bidirectional"))
    )
    (net (code "50") (name "/~{INT_REQ}") (class "Default")
      (node (ref "D145") (pin "C") (pinfunction "C_C") (pintype "passive"))
      (node (ref "D146") (pin "A") (pinfunction "A_A") (pintype "passive"))
      (node (ref "R97") (pin "1") (pinfunction "1_1") (pintype "passive"))
      (node (ref "U$2") (pin "CP1") (pinfunction "1_CP1") (pintype "bidirectional"))
    )
    (net (code "51") (name "/~{INT_STROBE}") (class "Default")
      (node (ref "D96") (pin "A") (pinfunction "A_A") (pintype "passive"))
      (node (ref "E1") (pin "11") (pinfunction "O_11") (pintype "output"))
      (node (ref "T1") (pin "15") (pinfunction "P$5_15") (pintype "passive"))
    )
    (net (code "52") (name "/~{IR0}") (class "Default")
      (node (ref "D167") (pin "C") (pinfunction "C_C") (pintype "passive"))
      (node (ref "D168") (pin "A") (pinfunction "A_A") (pintype "passive"))
      (node (ref "R108") (pin "1") (pinfunction "1_1") (pintype "passive"))
      (node (ref "U$2") (pin "DD2") (pinfunction "1_DD2") (pintype "bidirectional"))
    )
    (net (code "53") (name "/~{IR1}") (class "Default")
      (node (ref "D169") (pin "C") (pinfunction "C_C") (pintype "passive"))
      (node (ref "D170") (pin "A") (pinfunction "A_A") (pintype "passive"))
      (node (ref "R109") (pin "1") (pinfunction "1_1") (pintype "passive"))
      (node (ref "U$2") (pin "DE2") (pinfunction "1_DE2") (pintype "bidirectional"))
    )
    (net (code "54") (name "/~{IR2}") (class "Default")
      (node (ref "D171") (pin "C") (pinfunction "C_C") (pintype "passive"))
      (node (ref "D172") (pin "A") (pinfunction "A_A") (pintype "passive"))
      (node (ref "R110") (pin "1") (pinfunction "1_1") (pintype "passive"))
      (node (ref "U$2") (pin "DH2") (pinfunction "1_DH2") (pintype "bidirectional"))
    )
    (net (code "55") (name "/~{KEY_CTL}") (class "Default")
      (node (ref "D163") (pin "C") (pinfunction "C_C") (pintype "passive"))
      (node (ref "D164") (pin "A") (pinfunction "A_A") (pintype "passive"))
      (node (ref "R106") (pin "1") (pinfunction "1_1") (pintype "passive"))
      (node (ref "U$2") (pin "DU2") (pinfunction "1_DU2") (pintype "bidirectional"))
    )
    (net (code "56") (name "/~{LA_ENABLE}") (class "Default")
      (node (ref "D115") (pin "C") (pinfunction "C_C") (pintype "passive"))
      (node (ref "D116") (pin "A") (pinfunction "A_A") (pintype "passive"))
      (node (ref "R83") (pin "1") (pinfunction "1_1") (pintype "passive"))
      (node (ref "U$2") (pin "BM2") (pinfunction "1_BM2") (pintype "bidirectional"))
    )
    (net (code "57") (name "/~{LINK_DATA}") (class "Default")
      (node (ref "D149") (pin "C") (pinfunction "C_C") (pintype "passive"))
      (node (ref "D150") (pin "A") (pinfunction "A_A") (pintype "passive"))
      (node (ref "R99") (pin "1") (pinfunction "1_1") (pintype "passive"))
      (node (ref "U$2") (pin "CR2") (pinfunction "1_CR2") (pintype "bidirectional"))
    )
    (net (code "58") (name "/~{LINK_LOAD}") (class "Default")
      (node (ref "D192") (pin "C") (pinfunction "C_C") (pintype "passive"))
      (node (ref "R125") (pin "1") (pinfunction "1_1") (pintype "passive"))
      (node (ref "R127") (pin "2") (pinfunction "2_2") (pintype "passive"))
      (node (ref "U$2") (pin "CS2") (pinfunction "1_CS2") (pintype "bidirectional"))
    )
    (net (code "59") (name "/~{LINK}") (class "Default")
      (node (ref "D109") (pin "C") (pinfunction "C_C") (pintype "passive"))
      (node (ref "D110") (pin "A") (pinfunction "A_A") (pintype "passive"))
      (node (ref "R80") (pin "1") (pinfunction "1_1") (pintype "passive"))
      (node (ref "U$2") (pin "AV2") (pinfunction "1_AV2") (pintype "bidirectional"))
    )
    (net (code "60") (name "/~{MA0}") (class "Default")
      (node (ref "D18") (pin "C") (pinfunction "C_C") (pintype "passive"))
      (node (ref "D19") (pin "A") (pinfunction "A_A") (pintype "passive"))
      (node (ref "R33") (pin "1") (pinfunction "1_1") (pintype "passive"))
      (node (ref "U$2") (pin "AD1") (pinfunction "1_AD1") (pintype "bidirectional"))
    )
    (net (code "61") (name "/~{MA1}") (class "Default")
      (node (ref "D20") (pin "C") (pinfunction "C_C") (pintype "passive"))
      (node (ref "D21") (pin "A") (pinfunction "A_A") (pintype "passive"))
      (node (ref "R34") (pin "1") (pinfunction "1_1") (pintype "passive"))
      (node (ref "U$2") (pin "AE1") (pinfunction "1_AE1") (pintype "bidirectional"))
    )
    (net (code "62") (name "/~{MA2}") (class "Default")
      (node (ref "D22") (pin "C") (pinfunction "C_C") (pintype "passive"))
      (node (ref "D23") (pin "A") (pinfunction "A_A") (pintype "passive"))
      (node (ref "R35") (pin "1") (pinfunction "1_1") (pintype "passive"))
      (node (ref "U$2") (pin "AH1") (pinfunction "1_AH1") (pintype "bidirectional"))
    )
    (net (code "63") (name "/~{MA3}") (class "Default")
      (node (ref "D24") (pin "C") (pinfunction "C_C") (pintype "passive"))
      (node (ref "D25") (pin "A") (pinfunction "A_A") (pintype "passive"))
      (node (ref "R36") (pin "1") (pinfunction "1_1") (pintype "passive"))
      (node (ref "U$2") (pin "AJ1") (pinfunction "1_AJ1") (pintype "bidirectional"))
    )
    (net (code "64") (name "/~{MA4}") (class "Default")
      (node (ref "D34") (pin "C") (pinfunction "C_C") (pintype "passive"))
      (node (ref "D35") (pin "A") (pinfunction "A_A") (pintype "passive"))
      (node (ref "R41") (pin "1") (pinfunction "1_1") (pintype "passive"))
      (node (ref "U$2") (pin "BD1") (pinfunction "1_BD1") (pintype "bidirectional"))
    )
    (net (code "65") (name "/~{MA5}") (class "Default")
      (node (ref "D36") (pin "C") (pinfunction "C_C") (pintype "passive"))
      (node (ref "D37") (pin "A") (pinfunction "A_A") (pintype "passive"))
      (node (ref "R42") (pin "1") (pinfunction "1_1") (pintype "passive"))
      (node (ref "U$2") (pin "BE1") (pinfunction "1_BE1") (pintype "bidirectional"))
    )
    (net (code "66") (name "/~{MA6}") (class "Default")
      (node (ref "D38") (pin "C") (pinfunction "C_C") (pintype "passive"))
      (node (ref "D39") (pin "A") (pinfunction "A_A") (pintype "passive"))
      (node (ref "R43") (pin "1") (pinfunction "1_1") (pintype "passive"))
      (node (ref "U$2") (pin "BH1") (pinfunction "1_BH1") (pintype "bidirectional"))
    )
    (net (code "67") (name "/~{MA7}") (class "Default")
      (node (ref "D40") (pin "C") (pinfunction "C_C") (pintype "passive"))
      (node (ref "D41") (pin "A") (pinfunction "A_A") (pintype "passive"))
      (node (ref "R44") (pin "1") (pinfunction "1_1") (pintype "passive"))
      (node (ref "U$2") (pin "BJ1") (pinfunction "1_BJ1") (pintype "bidirectional"))
    )
    (net (code "68") (name "/~{MA8}") (class "Default")
      (node (ref "D44") (pin "C") (pinfunction "C_C") (pintype "passive"))
      (node (ref "D45") (pin "A") (pinfunction "A_A") (pintype "passive"))
      (node (ref "R46") (pin "1") (pinfunction "1_1") (pintype "passive"))
      (node (ref "U$2") (pin "DD1") (pinfunction "1_DD1") (pintype "bidirectional"))
    )
    (net (code "69") (name "/~{MA9}") (class "Default")
      (node (ref "D46") (pin "C") (pinfunction "C_C") (pintype "passive"))
      (node (ref "D47") (pin "A") (pinfunction "A_A") (pintype "passive"))
      (node (ref "R47") (pin "1") (pinfunction "1_1") (pintype "passive"))
      (node (ref "U$2") (pin "DE1") (pinfunction "1_DE1") (pintype "bidirectional"))
    )
    (net (code "70") (name "/~{MA10}") (class "Default")
      (node (ref "D48") (pin "C") (pinfunction "C_C") (pintype "passive"))
      (node (ref "D49") (pin "A") (pinfunction "A_A") (pintype "passive"))
      (node (ref "R48") (pin "1") (pinfunction "1_1") (pintype "passive"))
      (node (ref "U$2") (pin "DH1") (pinfunction "1_DH1") (pintype "bidirectional"))
    )
    (net (code "71") (name "/~{MA11}") (class "Default")
      (node (ref "D50") (pin "C") (pinfunction "C_C") (pintype "passive"))
      (node (ref "D51") (pin "A") (pinfunction "A_A") (pintype "passive"))
      (node (ref "R49") (pin "1") (pinfunction "1_1") (pintype "passive"))
      (node (ref "U$2") (pin "DJ1") (pinfunction "1_DJ1") (pintype "bidirectional"))
    )
    (net (code "72") (name "/~{MAMS_L_CTL}") (class "Default")
      (node (ref "D125") (pin "C") (pinfunction "C_C") (pintype "passive"))
      (node (ref "D126") (pin "A") (pinfunction "A_A") (pintype "passive"))
      (node (ref "R88") (pin "1") (pinfunction "1_1") (pintype "passive"))
      (node (ref "U$2") (pin "BH2") (pinfunction "1_BH2") (pintype "bidirectional"))
    )
    (net (code "73") (name "/~{MD0}") (class "Default")
      (node (ref "D100") (pin "A") (pinfunction "A_A") (pintype "passive"))
      (node (ref "D99") (pin "C") (pinfunction "C_C") (pintype "passive"))
      (node (ref "R75") (pin "1") (pinfunction "1_1") (pintype "passive"))
      (node (ref "U$2") (pin "AK1") (pinfunction "1_AK1") (pintype "bidirectional"))
    )
    (net (code "74") (name "/~{MD1}") (class "Default")
      (node (ref "D101") (pin "C") (pinfunction "C_C") (pintype "passive"))
      (node (ref "D102") (pin "A") (pinfunction "A_A") (pintype "passive"))
      (node (ref "R76") (pin "1") (pinfunction "1_1") (pintype "passive"))
      (node (ref "U$2") (pin "AL1") (pinfunction "1_AL1") (pintype "bidirectional"))
    )
    (net (code "75") (name "/~{MD2}") (class "Default")
      (node (ref "D103") (pin "C") (pinfunction "C_C") (pintype "passive"))
      (node (ref "D104") (pin "A") (pinfunction "A_A") (pintype "passive"))
      (node (ref "R77") (pin "1") (pinfunction "1_1") (pintype "passive"))
      (node (ref "U$2") (pin "AM1") (pinfunction "1_AM1") (pintype "bidirectional"))
    )
    (net (code "76") (name "/~{MD3}") (class "Default")
      (node (ref "D105") (pin "C") (pinfunction "C_C") (pintype "passive"))
      (node (ref "D106") (pin "A") (pinfunction "A_A") (pintype "passive"))
      (node (ref "R78") (pin "1") (pinfunction "1_1") (pintype "passive"))
      (node (ref "U$2") (pin "AP1") (pinfunction "1_AP1") (pintype "bidirectional"))
    )
    (net (code "77") (name "/~{MD4}") (class "Default")
      (node (ref "D117") (pin "C") (pinfunction "C_C") (pintype "passive"))
      (node (ref "D118") (pin "A") (pinfunction "A_A") (pintype "passive"))
      (node (ref "R84") (pin "1") (pinfunction "1_1") (pintype "passive"))
      (node (ref "U$2") (pin "BK1") (pinfunction "1_BK1") (pintype "bidirectional"))
    )
    (net (code "78") (name "/~{MD5}") (class "Default")
      (node (ref "D119") (pin "C") (pinfunction "C_C") (pintype "passive"))
      (node (ref "D120") (pin "A") (pinfunction "A_A") (pintype "passive"))
      (node (ref "R85") (pin "1") (pinfunction "1_1") (pintype "passive"))
      (node (ref "U$2") (pin "BL1") (pinfunction "1_BL1") (pintype "bidirectional"))
    )
    (net (code "79") (name "/~{MD6}") (class "Default")
      (node (ref "D121") (pin "C") (pinfunction "C_C") (pintype "passive"))
      (node (ref "D122") (pin "A") (pinfunction "A_A") (pintype "passive"))
      (node (ref "R86") (pin "1") (pinfunction "1_1") (pintype "passive"))
      (node (ref "U$2") (pin "BM1") (pinfunction "1_BM1") (pintype "bidirectional"))
    )
    (net (code "80") (name "/~{MD7}") (class "Default")
      (node (ref "D123") (pin "C") (pinfunction "C_C") (pintype "passive"))
      (node (ref "D124") (pin "A") (pinfunction "A_A") (pintype "passive"))
      (node (ref "R87") (pin "1") (pinfunction "1_1") (pintype "passive"))
      (node (ref "U$2") (pin "BP1") (pinfunction "1_BP1") (pintype "bidirectional"))
    )
    (net (code "81") (name "/~{MD8}") (class "Default")
      (node (ref "D175") (pin "C") (pinfunction "C_C") (pintype "passive"))
      (node (ref "D176") (pin "A") (pinfunction "A_A") (pintype "passive"))
      (node (ref "R112") (pin "1") (pinfunction "1_1") (pintype "passive"))
      (node (ref "U$2") (pin "DK1") (pinfunction "1_DK1") (pintype "bidirectional"))
    )
    (net (code "82") (name "/~{MD9}") (class "Default")
      (node (ref "D177") (pin "C") (pinfunction "C_C") (pintype "passive"))
      (node (ref "D178") (pin "A") (pinfunction "A_A") (pintype "passive"))
      (node (ref "R113") (pin "1") (pinfunction "1_1") (pintype "passive"))
      (node (ref "U$2") (pin "DL1") (pinfunction "1_DL1") (pintype "bidirectional"))
    )
    (net (code "83") (name "/~{MD10}") (class "Default")
      (node (ref "D179") (pin "C") (pinfunction "C_C") (pintype "passive"))
      (node (ref "D180") (pin "A") (pinfunction "A_A") (pintype "passive"))
      (node (ref "R114") (pin "1") (pinfunction "1_1") (pintype "passive"))
      (node (ref "U$2") (pin "DM1") (pinfunction "1_DM1") (pintype "bidirectional"))
    )
    (net (code "84") (name "/~{MD11}") (class "Default")
      (node (ref "D181") (pin "C") (pinfunction "C_C") (pintype "passive"))
      (node (ref "D182") (pin "A") (pinfunction "A_A") (pintype "passive"))
      (node (ref "R115") (pin "1") (pinfunction "1_1") (pintype "passive"))
      (node (ref "U$2") (pin "DP1") (pinfunction "1_DP1") (pintype "bidirectional"))
    )
    (net (code "85") (name "/~{MEM_DIR_IN}") (class "Default")
      (node (ref "D64") (pin "C") (pinfunction "C_C") (pintype "passive"))
      (node (ref "D65") (pin "A") (pinfunction "A_A") (pintype "passive"))
      (node (ref "R56") (pin "1") (pinfunction "1_1") (pintype "passive"))
      (node (ref "U$2") (pin "AK2") (pinfunction "1_AK2") (pintype "bidirectional"))
    )
    (net (code "86") (name "/~{MEM_START}") (class "Default")
      (node (ref "D107") (pin "C") (pinfunction "C_C") (pintype "passive"))
      (node (ref "D108") (pin "A") (pinfunction "A_A") (pintype "passive"))
      (node (ref "R79") (pin "1") (pinfunction "1_1") (pintype "passive"))
      (node (ref "U$2") (pin "AJ2") (pinfunction "1_AJ2") (pintype "bidirectional"))
    )
    (net (code "87") (name "/~{MS_IR_DISABL}") (class "Default")
      (node (ref "D42") (pin "C") (pinfunction "C_C") (pintype "passive"))
      (node (ref "D43") (pin "A") (pinfunction "A_A") (pintype "passive"))
      (node (ref "R45") (pin "1") (pinfunction "1_1") (pintype "passive"))
      (node (ref "U$2") (pin "CV1") (pinfunction "1_CV1") (pintype "bidirectional"))
    )
    (net (code "88") (name "/~{NOT_LST_XFR}") (class "Default")
      (node (ref "D157") (pin "C") (pinfunction "C_C") (pintype "passive"))
      (node (ref "D158") (pin "A") (pinfunction "A_A") (pintype "passive"))
      (node (ref "R103") (pin "1") (pinfunction "1_1") (pintype "passive"))
      (node (ref "U$2") (pin "CM1") (pinfunction "1_CM1") (pintype "bidirectional"))
    )
    (net (code "89") (name "/~{OVERFLOW}") (class "Default")
      (node (ref "D113") (pin "C") (pinfunction "C_C") (pintype "passive"))
      (node (ref "D114") (pin "A") (pinfunction "A_A") (pintype "passive"))
      (node (ref "R82") (pin "1") (pinfunction "1_1") (pintype "passive"))
      (node (ref "U$2") (pin "BJ2") (pinfunction "1_BJ2") (pintype "bidirectional"))
    )
    (net (code "90") (name "/~{PAUSE}") (class "Default")
      (node (ref "D15") (pin "C") (pinfunction "C_C") (pintype "passive"))
      (node (ref "R29") (pin "1") (pinfunction "1_1") (pintype "passive"))
      (node (ref "R30") (pin "2") (pinfunction "2_2") (pintype "passive"))
      (node (ref "U$2") (pin "CD1") (pinfunction "1_CD1") (pintype "bidirectional"))
    )
    (net (code "91") (name "/~{ROM_ADDR}") (class "Default")
      (node (ref "D32") (pin "C") (pinfunction "C_C") (pintype "passive"))
      (node (ref "D33") (pin "A") (pinfunction "A_A") (pintype "passive"))
      (node (ref "R40") (pin "1") (pinfunction "1_1") (pintype "passive"))
      (node (ref "U$2") (pin "AU2") (pinfunction "1_AU2") (pintype "bidirectional"))
    )
    (net (code "92") (name "/~{RUN}") (class "Default")
      (node (ref "D196") (pin "C") (pinfunction "C_C") (pintype "passive"))
      (node (ref "U$2") (pin "BU2") (pinfunction "1_BU2") (pintype "bidirectional"))
    )
    (net (code "93") (name "/~{SKIP}") (class "Default")
      (node (ref "D147") (pin "C") (pinfunction "C_C") (pintype "passive"))
      (node (ref "D148") (pin "A") (pinfunction "A_A") (pintype "passive"))
      (node (ref "R98") (pin "1") (pinfunction "1_1") (pintype "passive"))
      (node (ref "U$2") (pin "CS1") (pinfunction "1_CS1") (pintype "bidirectional"))
    )
    (net (code "94") (name "/~{STOP}") (class "Default")
      (node (ref "D161") (pin "C") (pinfunction "C_C") (pintype "passive"))
      (node (ref "D162") (pin "A") (pinfunction "A_A") (pintype "passive"))
      (node (ref "D193") (pin "A") (pinfunction "A_A") (pintype "passive"))
      (node (ref "R105") (pin "1") (pinfunction "1_1") (pintype "passive"))
      (node (ref "U$2") (pin "DS2") (pinfunction "1_DS2") (pintype "bidirectional"))
    )
    (net (code "95") (name "/~{SW}") (class "Default")
      (node (ref "D165") (pin "C") (pinfunction "C_C") (pintype "passive"))
      (node (ref "D166") (pin "A") (pinfunction "A_A") (pintype "passive"))
      (node (ref "R107") (pin "1") (pinfunction "1_1") (pintype "passive"))
      (node (ref "U$2") (pin "DV2") (pinfunction "1_DV2") (pintype "bidirectional"))
    )
    (net (code "96") (name "/~{TP2}") (class "Default")
      (node (ref "D62") (pin "A") (pinfunction "A_A") (pintype "passive"))
      (node (ref "E1") (pin "8") (pinfunction "O_8") (pintype "output"))
      (node (ref "T1") (pin "13") (pinfunction "P$5_13") (pintype "passive"))
    )
    (net (code "97") (name "/~{TP4}") (class "Default")
      (node (ref "D16") (pin "A") (pinfunction "A_A") (pintype "passive"))
      (node (ref "E1") (pin "6") (pinfunction "O_6") (pintype "output"))
      (node (ref "T1") (pin "9") (pinfunction "P$5_9") (pintype "passive"))
    )
    (net (code "98") (name "/~{TS1}") (class "Default")
      (node (ref "D5") (pin "C") (pinfunction "C_C") (pintype "passive"))
      (node (ref "R10") (pin "2") (pinfunction "2_2") (pintype "passive"))
      (node (ref "R9") (pin "1") (pinfunction "1_1") (pintype "passive"))
      (node (ref "U$2") (pin "CK2") (pinfunction "1_CK2") (pintype "bidirectional"))
    )
    (net (code "99") (name "/~{TS2}") (class "Default")
      (node (ref "D6") (pin "C") (pinfunction "C_C") (pintype "passive"))
      (node (ref "R11") (pin "1") (pinfunction "1_1") (pintype "passive"))
      (node (ref "R12") (pin "2") (pinfunction "2_2") (pintype "passive"))
      (node (ref "U$2") (pin "CL2") (pinfunction "1_CL2") (pintype "bidirectional"))
    )
    (net (code "100") (name "/~{TS3}") (class "Default")
      (node (ref "D7") (pin "C") (pinfunction "C_C") (pintype "passive"))
      (node (ref "R13") (pin "1") (pinfunction "1_1") (pintype "passive"))
      (node (ref "R14") (pin "2") (pinfunction "2_2") (pintype "passive"))
      (node (ref "U$2") (pin "CM2") (pinfunction "1_CM2") (pintype "bidirectional"))
    )
    (net (code "101") (name "/~{TS4}") (class "Default")
      (node (ref "D8") (pin "C") (pinfunction "C_C") (pintype "passive"))
      (node (ref "R15") (pin "1") (pinfunction "1_1") (pintype "passive"))
      (node (ref "R16") (pin "2") (pinfunction "2_2") (pintype "passive"))
      (node (ref "U$2") (pin "CP2") (pinfunction "1_CP2") (pintype "bidirectional"))
    )
    (net (code "102") (name "/~{USER_MODE}") (class "Default")
      (node (ref "D183") (pin "C") (pinfunction "C_C") (pintype "passive"))
      (node (ref "D184") (pin "A") (pinfunction "A_A") (pintype "passive"))
      (node (ref "R116") (pin "1") (pinfunction "1_1") (pintype "passive"))
      (node (ref "U$2") (pin "DM2") (pinfunction "1_DM2") (pintype "bidirectional"))
    )
    (net (code "103") (name "GND") (class "Default")
      (node (ref "C1") (pin "2") (pinfunction "2_2") (pintype "passive"))
      (node (ref "C10") (pin "2") (pinfunction "2_2") (pintype "passive"))
      (node (ref "C11") (pin "-") (pinfunction "-_-") (pintype "passive"))
      (node (ref "C12") (pin "-") (pinfunction "-_-") (pintype "passive"))
      (node (ref "C13") (pin "-") (pinfunction "-_-") (pintype "passive"))
      (node (ref "C14") (pin "1") (pinfunction "1_1") (pintype "passive"))
      (node (ref "C15") (pin "2") (pinfunction "2_2") (pintype "passive"))
      (node (ref "C16") (pin "2") (pinfunction "2_2") (pintype "passive"))
      (node (ref "C17") (pin "2") (pinfunction "2_2") (pintype "passive"))
      (node (ref "C18") (pin "2") (pinfunction "2_2") (pintype "passive"))
      (node (ref "C19") (pin "-") (pinfunction "-_-") (pintype "passive"))
      (node (ref "C2") (pin "-") (pinfunction "-_-") (pintype "passive"))
      (node (ref "C20") (pin "2") (pinfunction "2_2") (pintype "passive"))
      (node (ref "C21") (pin "2") (pinfunction "2_2") (pintype "passive"))
      (node (ref "C22") (pin "2") (pinfunction "2_2") (pintype "passive"))
      (node (ref "C23") (pin "2") (pinfunction "2_2") (pintype "passive"))
      (node (ref "C24") (pin "2") (pinfunction "2_2") (pintype "passive"))
      (node (ref "C25") (pin "2") (pinfunction "2_2") (pintype "passive"))
      (node (ref "C26") (pin "-") (pinfunction "-_-") (pintype "passive"))
      (node (ref "C27") (pin "2") (pinfunction "2_2") (pintype "passive"))
      (node (ref "C28") (pin "2") (pinfunction "2_2") (pintype "passive"))
      (node (ref "C29") (pin "2") (pinfunction "2_2") (pintype "passive"))
      (node (ref "C3") (pin "2") (pinfunction "2_2") (pintype "passive"))
      (node (ref "C31") (pin "2") (pinfunction "2_2") (pintype "passive"))
      (node (ref "C32") (pin "2") (pinfunction "2_2") (pintype "passive"))
      (node (ref "C33") (pin "-") (pinfunction "-_-") (pintype "passive"))
      (node (ref "C4") (pin "2") (pinfunction "2_2") (pintype "passive"))
      (node (ref "C5") (pin "2") (pinfunction "2_2") (pintype "passive"))
      (node (ref "C6") (pin "2") (pinfunction "2_2") (pintype "passive"))
      (node (ref "C7") (pin "2") (pinfunction "2_2") (pintype "passive"))
      (node (ref "C8") (pin "2") (pinfunction "2_2") (pintype "passive"))
      (node (ref "C9") (pin "2") (pinfunction "2_2") (pintype "passive"))
      (node (ref "D1") (pin "A") (pinfunction "A_A") (pintype "passive"))
      (node (ref "D10") (pin "A") (pinfunction "A_A") (pintype "passive"))
      (node (ref "D101") (pin "A") (pinfunction "A_A") (pintype "passive"))
      (node (ref "D103") (pin "A") (pinfunction "A_A") (pintype "passive"))
      (node (ref "D105") (pin "A") (pinfunction "A_A") (pintype "passive"))
      (node (ref "D107") (pin "A") (pinfunction "A_A") (pintype "passive"))
      (node (ref "D109") (pin "A") (pinfunction "A_A") (pintype "passive"))
      (node (ref "D11") (pin "A") (pinfunction "A_A") (pintype "passive"))
      (node (ref "D111") (pin "A") (pinfunction "A_A") (pintype "passive"))
      (node (ref "D113") (pin "A") (pinfunction "A_A") (pintype "passive"))
      (node (ref "D115") (pin "A") (pinfunction "A_A") (pintype "passive"))
      (node (ref "D117") (pin "A") (pinfunction "A_A") (pintype "passive"))
      (node (ref "D119") (pin "A") (pinfunction "A_A") (pintype "passive"))
      (node (ref "D12") (pin "A") (pinfunction "A_A") (pintype "passive"))
      (node (ref "D121") (pin "A") (pinfunction "A_A") (pintype "passive"))
      (node (ref "D123") (pin "A") (pinfunction "A_A") (pintype "passive"))
      (node (ref "D125") (pin "A") (pinfunction "A_A") (pintype "passive"))
      (node (ref "D127") (pin "A") (pinfunction "A_A") (pintype "passive"))
      (node (ref "D129") (pin "A") (pinfunction "A_A") (pintype "passive"))
      (node (ref "D13") (pin "A") (pinfunction "A_A") (pintype "passive"))
      (node (ref "D131") (pin "A") (pinfunction "A_A") (pintype "passive"))
      (node (ref "D133") (pin "A") (pinfunction "A_A") (pintype "passive"))
      (node (ref "D135") (pin "A") (pinfunction "A_A") (pintype "passive"))
      (node (ref "D137") (pin "A") (pinfunction "A_A") (pintype "passive"))
      (node (ref "D139") (pin "A") (pinfunction "A_A") (pintype "passive"))
      (node (ref "D14") (pin "A") (pinfunction "A_A") (pintype "passive"))
      (node (ref "D141") (pin "C") (pinfunction "C_C") (pintype "passive"))
      (node (ref "D145") (pin "A") (pinfunction "A_A") (pintype "passive"))
      (node (ref "D147") (pin "A") (pinfunction "A_A") (pintype "passive"))
      (node (ref "D149") (pin "A") (pinfunction "A_A") (pintype "passive"))
      (node (ref "D15") (pin "A") (pinfunction "A_A") (pintype "passive"))
      (node (ref "D151") (pin "A") (pinfunction "A_A") (pintype "passive"))
      (node (ref "D153") (pin "A") (pinfunction "A_A") (pintype "passive"))
      (node (ref "D155") (pin "A") (pinfunction "A_A") (pintype "passive"))
      (node (ref "D157") (pin "A") (pinfunction "A_A") (pintype "passive"))
      (node (ref "D159") (pin "A") (pinfunction "A_A") (pintype "passive"))
      (node (ref "D161") (pin "A") (pinfunction "A_A") (pintype "passive"))
      (node (ref "D163") (pin "A") (pinfunction "A_A") (pintype "passive"))
      (node (ref "D165") (pin "A") (pinfunction "A_A") (pintype "passive"))
      (node (ref "D167") (pin "A") (pinfunction "A_A") (pintype "passive"))
      (node (ref "D169") (pin "A") (pinfunction "A_A") (pintype "passive"))
      (node (ref "D171") (pin "A") (pinfunction "A_A") (pintype "passive"))
      (node (ref "D173") (pin "A") (pinfunction "A_A") (pintype "passive"))
      (node (ref "D175") (pin "A") (pinfunction "A_A") (pintype "passive"))
      (node (ref "D177") (pin "A") (pinfunction "A_A") (pintype "passive"))
      (node (ref "D179") (pin "A") (pinfunction "A_A") (pintype "passive"))
      (node (ref "D18") (pin "A") (pinfunction "A_A") (pintype "passive"))
      (node (ref "D181") (pin "A") (pinfunction "A_A") (pintype "passive"))
      (node (ref "D183") (pin "A") (pinfunction "A_A") (pintype "passive"))
      (node (ref "D185") (pin "C") (pinfunction "C_C") (pintype "passive"))
      (node (ref "D189") (pin "A") (pinfunction "A_A") (pintype "passive"))
      (node (ref "D190") (pin "A") (pinfunction "A_A") (pintype "passive"))
      (node (ref "D191") (pin "A") (pinfunction "A_A") (pintype "passive"))
      (node (ref "D192") (pin "A") (pinfunction "A_A") (pintype "passive"))
      (node (ref "D194") (pin "A") (pinfunction "A_A") (pintype "passive"))
      (node (ref "D196") (pin "A") (pinfunction "A_A") (pintype "passive"))
      (node (ref "D2") (pin "A") (pinfunction "A_A") (pintype "passive"))
      (node (ref "D20") (pin "A") (pinfunction "A_A") (pintype "passive"))
      (node (ref "D22") (pin "A") (pinfunction "A_A") (pintype "passive"))
      (node (ref "D24") (pin "A") (pinfunction "A_A") (pintype "passive"))
      (node (ref "D26") (pin "A") (pinfunction "A_A") (pintype "passive"))
      (node (ref "D28") (pin "A") (pinfunction "A_A") (pintype "passive"))
      (node (ref "D3") (pin "A") (pinfunction "A_A") (pintype "passive"))
      (node (ref "D30") (pin "A") (pinfunction "A_A") (pintype "passive"))
      (node (ref "D32") (pin "A") (pinfunction "A_A") (pintype "passive"))
      (node (ref "D34") (pin "A") (pinfunction "A_A") (pintype "passive"))
      (node (ref "D36") (pin "A") (pinfunction "A_A") (pintype "passive"))
      (node (ref "D38") (pin "A") (pinfunction "A_A") (pintype "passive"))
      (node (ref "D4") (pin "A") (pinfunction "A_A") (pintype "passive"))
      (node (ref "D40") (pin "A") (pinfunction "A_A") (pintype "passive"))
      (node (ref "D42") (pin "A") (pinfunction "A_A") (pintype "passive"))
      (node (ref "D44") (pin "A") (pinfunction "A_A") (pintype "passive"))
      (node (ref "D46") (pin "A") (pinfunction "A_A") (pintype "passive"))
      (node (ref "D48") (pin "A") (pinfunction "A_A") (pintype "passive"))
      (node (ref "D5") (pin "A") (pinfunction "A_A") (pintype "passive"))
      (node (ref "D50") (pin "A") (pinfunction "A_A") (pintype "passive"))
      (node (ref "D52") (pin "A") (pinfunction "A_A") (pintype "passive"))
      (node (ref "D54") (pin "A") (pinfunction "A_A") (pintype "passive"))
      (node (ref "D56") (pin "A") (pinfunction "A_A") (pintype "passive"))
      (node (ref "D58") (pin "C") (pinfunction "C_C") (pintype "passive"))
      (node (ref "D6") (pin "A") (pinfunction "A_A") (pintype "passive"))
      (node (ref "D64") (pin "A") (pinfunction "A_A") (pintype "passive"))
      (node (ref "D66") (pin "C") (pinfunction "C_C") (pintype "passive"))
      (node (ref "D7") (pin "A") (pinfunction "A_A") (pintype "passive"))
      (node (ref "D70") (pin "A") (pinfunction "A_A") (pintype "passive"))
      (node (ref "D72") (pin "A") (pinfunction "A_A") (pintype "passive"))
      (node (ref "D74") (pin "A") (pinfunction "A_A") (pintype "passive"))
      (node (ref "D76") (pin "A") (pinfunction "A_A") (pintype "passive"))
      (node (ref "D78") (pin "A") (pinfunction "A_A") (pintype "passive"))
      (node (ref "D8") (pin "A") (pinfunction "A_A") (pintype "passive"))
      (node (ref "D80") (pin "A") (pinfunction "A_A") (pintype "passive"))
      (node (ref "D82") (pin "A") (pinfunction "A_A") (pintype "passive"))
      (node (ref "D84") (pin "A") (pinfunction "A_A") (pintype "passive"))
      (node (ref "D86") (pin "A") (pinfunction "A_A") (pintype "passive"))
      (node (ref "D88") (pin "A") (pinfunction "A_A") (pintype "passive"))
      (node (ref "D9") (pin "A") (pinfunction "A_A") (pintype "passive"))
      (node (ref "D90") (pin "A") (pinfunction "A_A") (pintype "passive"))
      (node (ref "D92") (pin "A") (pinfunction "A_A") (pintype "passive"))
      (node (ref "D94") (pin "A") (pinfunction "A_A") (pintype "passive"))
      (node (ref "D98") (pin "A") (pinfunction "A_A") (pintype "passive"))
      (node (ref "D99") (pin "A") (pinfunction "A_A") (pintype "passive"))
      (node (ref "E1") (pin "1") (pinfunction "I0_1") (pintype "input"))
      (node (ref "E1") (pin "2") (pinfunction "I1_2") (pintype "input"))
      (node (ref "R10") (pin "1") (pinfunction "1_1") (pintype "passive"))
      (node (ref "R12") (pin "1") (pinfunction "1_1") (pintype "passive"))
      (node (ref "R127") (pin "1") (pinfunction "1_1") (pintype "passive"))
      (node (ref "R128") (pin "1") (pinfunction "1_1") (pintype "passive"))
      (node (ref "R14") (pin "1") (pinfunction "1_1") (pintype "passive"))
      (node (ref "R16") (pin "1") (pinfunction "1_1") (pintype "passive"))
      (node (ref "R18") (pin "1") (pinfunction "1_1") (pintype "passive"))
      (node (ref "R2") (pin "1") (pinfunction "1_1") (pintype "passive"))
      (node (ref "R20") (pin "1") (pinfunction "1_1") (pintype "passive"))
      (node (ref "R22") (pin "1") (pinfunction "1_1") (pintype "passive"))
      (node (ref "R24") (pin "1") (pinfunction "1_1") (pintype "passive"))
      (node (ref "R26") (pin "1") (pinfunction "1_1") (pintype "passive"))
      (node (ref "R28") (pin "1") (pinfunction "1_1") (pintype "passive"))
      (node (ref "R30") (pin "1") (pinfunction "1_1") (pintype "passive"))
      (node (ref "R4") (pin "1") (pinfunction "1_1") (pintype "passive"))
      (node (ref "R6") (pin "1") (pinfunction "1_1") (pintype "passive"))
      (node (ref "R8") (pin "1") (pinfunction "1_1") (pintype "passive"))
      (node (ref "U$2") (pin "AC2") (pinfunction "1_AC2") (pintype "bidirectional"))
      (node (ref "U$2") (pin "AF1") (pinfunction "1_AF1") (pintype "bidirectional"))
      (node (ref "U$2") (pin "AF2") (pinfunction "1_AF2") (pintype "bidirectional"))
      (node (ref "U$2") (pin "AN1") (pinfunction "1_AN1") (pintype "bidirectional"))
      (node (ref "U$2") (pin "AN2") (pinfunction "1_AN2") (pintype "bidirectional"))
      (node (ref "U$2") (pin "AT1") (pinfunction "1_AT1") (pintype "bidirectional"))
      (node (ref "U$2") (pin "AT2") (pinfunction "1_AT2") (pintype "bidirectional"))
      (node (ref "U$2") (pin "BC1") (pinfunction "1_BC1") (pintype "bidirectional"))
      (node (ref "U$2") (pin "BC2") (pinfunction "1_BC2") (pintype "bidirectional"))
      (node (ref "U$2") (pin "BF1") (pinfunction "1_BF1") (pintype "bidirectional"))
      (node (ref "U$2") (pin "BF2") (pinfunction "1_BF2") (pintype "bidirectional"))
      (node (ref "U$2") (pin "BN1") (pinfunction "1_BN1") (pintype "bidirectional"))
      (node (ref "U$2") (pin "BN2") (pinfunction "1_BN2") (pintype "bidirectional"))
      (node (ref "U$2") (pin "BT1") (pinfunction "1_BT1") (pintype "bidirectional"))
      (node (ref "U$2") (pin "BT2") (pinfunction "1_BT2") (pintype "bidirectional"))
      (node (ref "U$2") (pin "CC1") (pinfunction "1_CC1") (pintype "bidirectional"))
      (node (ref "U$2") (pin "CC2") (pinfunction "1_CC2") (pintype "bidirectional"))
      (node (ref "U$2") (pin "CF1") (pinfunction "1_CF1") (pintype "bidirectional"))
      (node (ref "U$2") (pin "CF2") (pinfunction "1_CF2") (pintype "bidirectional"))
      (node (ref "U$2") (pin "CN1") (pinfunction "1_CN1") (pintype "bidirectional"))
      (node (ref "U$2") (pin "CN2") (pinfunction "1_CN2") (pintype "bidirectional"))
      (node (ref "U$2") (pin "CT1") (pinfunction "1_CT1") (pintype "bidirectional"))
      (node (ref "U$2") (pin "CT2") (pinfunction "1_CT2") (pintype "bidirectional"))
      (node (ref "U$2") (pin "DC1") (pinfunction "1_DC1") (pintype "bidirectional"))
      (node (ref "U$2") (pin "DC2") (pinfunction "1_DC2") (pintype "bidirectional"))
      (node (ref "U$2") (pin "DF1") (pinfunction "1_DF1") (pintype "bidirectional"))
      (node (ref "U$2") (pin "DF2") (pinfunction "1_DF2") (pintype "bidirectional"))
      (node (ref "U$2") (pin "DN1") (pinfunction "1_DN1") (pintype "bidirectional"))
      (node (ref "U$2") (pin "DN2") (pinfunction "1_DN2") (pintype "bidirectional"))
      (node (ref "U$2") (pin "DT1") (pinfunction "1_DT1") (pintype "bidirectional"))
      (node (ref "U$2") (pin "DT2") (pinfunction "1_DT2") (pintype "bidirectional"))
    )
    (net (code "104") (name "Net-(C4-Pad1)") (class "Default")
      (node (ref "C4") (pin "1") (pinfunction "1_1") (pintype "passive"))
      (node (ref "C6") (pin "1") (pinfunction "1_1") (pintype "passive"))
      (node (ref "D146") (pin "C") (pinfunction "C_C") (pintype "passive"))
      (node (ref "D148") (pin "C") (pinfunction "C_C") (pintype "passive"))
      (node (ref "D150") (pin "C") (pinfunction "C_C") (pintype "passive"))
      (node (ref "D152") (pin "C") (pinfunction "C_C") (pintype "passive"))
      (node (ref "D154") (pin "C") (pinfunction "C_C") (pintype "passive"))
      (node (ref "D156") (pin "C") (pinfunction "C_C") (pintype "passive"))
      (node (ref "D158") (pin "C") (pinfunction "C_C") (pintype "passive"))
      (node (ref "D160") (pin "C") (pinfunction "C_C") (pintype "passive"))
      (node (ref "D162") (pin "C") (pinfunction "C_C") (pintype "passive"))
      (node (ref "D164") (pin "C") (pinfunction "C_C") (pintype "passive"))
      (node (ref "D166") (pin "C") (pinfunction "C_C") (pintype "passive"))
      (node (ref "D168") (pin "C") (pinfunction "C_C") (pintype "passive"))
      (node (ref "D170") (pin "C") (pinfunction "C_C") (pintype "passive"))
      (node (ref "D172") (pin "C") (pinfunction "C_C") (pintype "passive"))
      (node (ref "D174") (pin "C") (pinfunction "C_C") (pintype "passive"))
      (node (ref "D176") (pin "C") (pinfunction "C_C") (pintype "passive"))
      (node (ref "D178") (pin "C") (pinfunction "C_C") (pintype "passive"))
      (node (ref "D180") (pin "C") (pinfunction "C_C") (pintype "passive"))
      (node (ref "D182") (pin "C") (pinfunction "C_C") (pintype "passive"))
      (node (ref "D184") (pin "C") (pinfunction "C_C") (pintype "passive"))
      (node (ref "D188") (pin "A") (pinfunction "A_A") (pintype "passive"))
      (node (ref "R117") (pin "1") (pinfunction "1_1") (pintype "passive"))
    )
    (net (code "105") (name "Net-(C15-Pad1)") (class "Default")
      (node (ref "C15") (pin "1") (pinfunction "1_1") (pintype "passive"))
      (node (ref "C31") (pin "1") (pinfunction "1_1") (pintype "passive"))
      (node (ref "D19") (pin "C") (pinfunction "C_C") (pintype "passive"))
      (node (ref "D21") (pin "C") (pinfunction "C_C") (pintype "passive"))
      (node (ref "D23") (pin "C") (pinfunction "C_C") (pintype "passive"))
      (node (ref "D25") (pin "C") (pinfunction "C_C") (pintype "passive"))
      (node (ref "D27") (pin "C") (pinfunction "C_C") (pintype "passive"))
      (node (ref "D29") (pin "C") (pinfunction "C_C") (pintype "passive"))
      (node (ref "D31") (pin "C") (pinfunction "C_C") (pintype "passive"))
      (node (ref "D33") (pin "C") (pinfunction "C_C") (pintype "passive"))
      (node (ref "D35") (pin "C") (pinfunction "C_C") (pintype "passive"))
      (node (ref "D37") (pin "C") (pinfunction "C_C") (pintype "passive"))
      (node (ref "D39") (pin "C") (pinfunction "C_C") (pintype "passive"))
      (node (ref "D41") (pin "C") (pinfunction "C_C") (pintype "passive"))
      (node (ref "D43") (pin "C") (pinfunction "C_C") (pintype "passive"))
      (node (ref "D45") (pin "C") (pinfunction "C_C") (pintype "passive"))
      (node (ref "D47") (pin "C") (pinfunction "C_C") (pintype "passive"))
      (node (ref "D49") (pin "C") (pinfunction "C_C") (pintype "passive"))
      (node (ref "D51") (pin "C") (pinfunction "C_C") (pintype "passive"))
      (node (ref "D53") (pin "C") (pinfunction "C_C") (pintype "passive"))
      (node (ref "D55") (pin "C") (pinfunction "C_C") (pintype "passive"))
      (node (ref "D57") (pin "C") (pinfunction "C_C") (pintype "passive"))
      (node (ref "D61") (pin "A") (pinfunction "A_A") (pintype "passive"))
      (node (ref "R53") (pin "1") (pinfunction "1_1") (pintype "passive"))
    )
    (net (code "106") (name "Net-(C17-Pad1)") (class "Default")
      (node (ref "C17") (pin "1") (pinfunction "1_1") (pintype "passive"))
      (node (ref "C23") (pin "1") (pinfunction "1_1") (pintype "passive"))
      (node (ref "D65") (pin "C") (pinfunction "C_C") (pintype "passive"))
      (node (ref "D69") (pin "A") (pinfunction "A_A") (pintype "passive"))
      (node (ref "D71") (pin "C") (pinfunction "C_C") (pintype "passive"))
      (node (ref "D73") (pin "C") (pinfunction "C_C") (pintype "passive"))
      (node (ref "D75") (pin "C") (pinfunction "C_C") (pintype "passive"))
      (node (ref "D77") (pin "C") (pinfunction "C_C") (pintype "passive"))
      (node (ref "D79") (pin "C") (pinfunction "C_C") (pintype "passive"))
      (node (ref "D81") (pin "C") (pinfunction "C_C") (pintype "passive"))
      (node (ref "D83") (pin "C") (pinfunction "C_C") (pintype "passive"))
      (node (ref "D85") (pin "C") (pinfunction "C_C") (pintype "passive"))
      (node (ref "D87") (pin "C") (pinfunction "C_C") (pintype "passive"))
      (node (ref "D89") (pin "C") (pinfunction "C_C") (pintype "passive"))
      (node (ref "D91") (pin "C") (pinfunction "C_C") (pintype "passive"))
      (node (ref "D93") (pin "C") (pinfunction "C_C") (pintype "passive"))
      (node (ref "D95") (pin "C") (pinfunction "C_C") (pintype "passive"))
      (node (ref "R70") (pin "1") (pinfunction "1_1") (pintype "passive"))
    )
    (net (code "107") (name "Net-(C20-Pad1)") (class "Default")
      (node (ref "C20") (pin "1") (pinfunction "1_1") (pintype "passive"))
      (node (ref "C8") (pin "1") (pinfunction "1_1") (pintype "passive"))
      (node (ref "D100") (pin "C") (pinfunction "C_C") (pintype "passive"))
      (node (ref "D102") (pin "C") (pinfunction "C_C") (pintype "passive"))
      (node (ref "D104") (pin "C") (pinfunction "C_C") (pintype "passive"))
      (node (ref "D106") (pin "C") (pinfunction "C_C") (pintype "passive"))
      (node (ref "D108") (pin "C") (pinfunction "C_C") (pintype "passive"))
      (node (ref "D110") (pin "C") (pinfunction "C_C") (pintype "passive"))
      (node (ref "D112") (pin "C") (pinfunction "C_C") (pintype "passive"))
      (node (ref "D114") (pin "C") (pinfunction "C_C") (pintype "passive"))
      (node (ref "D116") (pin "C") (pinfunction "C_C") (pintype "passive"))
      (node (ref "D118") (pin "C") (pinfunction "C_C") (pintype "passive"))
      (node (ref "D120") (pin "C") (pinfunction "C_C") (pintype "passive"))
      (node (ref "D122") (pin "C") (pinfunction "C_C") (pintype "passive"))
      (node (ref "D124") (pin "C") (pinfunction "C_C") (pintype "passive"))
      (node (ref "D126") (pin "C") (pinfunction "C_C") (pintype "passive"))
      (node (ref "D128") (pin "C") (pinfunction "C_C") (pintype "passive"))
      (node (ref "D130") (pin "C") (pinfunction "C_C") (pintype "passive"))
      (node (ref "D132") (pin "C") (pinfunction "C_C") (pintype "passive"))
      (node (ref "D134") (pin "C") (pinfunction "C_C") (pintype "passive"))
      (node (ref "D136") (pin "C") (pinfunction "C_C") (pintype "passive"))
      (node (ref "D138") (pin "C") (pinfunction "C_C") (pintype "passive"))
      (node (ref "D140") (pin "C") (pinfunction "C_C") (pintype "passive"))
      (node (ref "D144") (pin "A") (pinfunction "A_A") (pintype "passive"))
      (node (ref "R96") (pin "1") (pinfunction "1_1") (pintype "passive"))
    )
    (net (code "108") (name "Net-(C30-Pad1)") (class "Default")
      (node (ref "C30") (pin "1") (pinfunction "1_1") (pintype "passive"))
      (node (ref "D97") (pin "C") (pinfunction "C_C") (pintype "passive"))
      (node (ref "R57") (pin "2") (pinfunction "2_2") (pintype "passive"))
      (node (ref "R58") (pin "2") (pinfunction "2_2") (pintype "passive"))
      (node (ref "R59") (pin "2") (pinfunction "2_2") (pintype "passive"))
      (node (ref "R60") (pin "2") (pinfunction "2_2") (pintype "passive"))
      (node (ref "R61") (pin "2") (pinfunction "2_2") (pintype "passive"))
      (node (ref "R62") (pin "2") (pinfunction "2_2") (pintype "passive"))
      (node (ref "R63") (pin "2") (pinfunction "2_2") (pintype "passive"))
      (node (ref "R64") (pin "2") (pinfunction "2_2") (pintype "passive"))
      (node (ref "R65") (pin "2") (pinfunction "2_2") (pintype "passive"))
      (node (ref "R66") (pin "2") (pinfunction "2_2") (pintype "passive"))
      (node (ref "R67") (pin "2") (pinfunction "2_2") (pintype "passive"))
      (node (ref "R68") (pin "2") (pinfunction "2_2") (pintype "passive"))
      (node (ref "R69") (pin "2") (pinfunction "2_2") (pintype "passive"))
      (node (ref "R74") (pin "1") (pinfunction "1_1") (pintype "passive"))
    )
    (net (code "109") (name "Net-(D58-PadA)") (class "Default")
      (node (ref "D58") (pin "A") (pinfunction "A_A") (pintype "passive"))
      (node (ref "D59") (pin "C") (pinfunction "C_C") (pintype "passive"))
    )
    (net (code "110") (name "Net-(D59-PadA)") (class "Default")
      (node (ref "D59") (pin "A") (pinfunction "A_A") (pintype "passive"))
      (node (ref "D60") (pin "C") (pinfunction "C_C") (pintype "passive"))
    )
    (net (code "111") (name "Net-(D60-PadA)") (class "Default")
      (node (ref "D60") (pin "A") (pinfunction "A_A") (pintype "passive"))
      (node (ref "D61") (pin "C") (pinfunction "C_C") (pintype "passive"))
    )
    (net (code "112") (name "Net-(D66-PadA)") (class "Default")
      (node (ref "D66") (pin "A") (pinfunction "A_A") (pintype "passive"))
      (node (ref "D67") (pin "C") (pinfunction "C_C") (pintype "passive"))
    )
    (net (code "113") (name "Net-(D67-PadA)") (class "Default")
      (node (ref "D67") (pin "A") (pinfunction "A_A") (pintype "passive"))
      (node (ref "D68") (pin "C") (pinfunction "C_C") (pintype "passive"))
    )
    (net (code "114") (name "Net-(D68-PadA)") (class "Default")
      (node (ref "D68") (pin "A") (pinfunction "A_A") (pintype "passive"))
      (node (ref "D69") (pin "C") (pinfunction "C_C") (pintype "passive"))
    )
    (net (code "115") (name "Net-(D141-PadA)") (class "Default")
      (node (ref "D141") (pin "A") (pinfunction "A_A") (pintype "passive"))
      (node (ref "D142") (pin "C") (pinfunction "C_C") (pintype "passive"))
    )
    (net (code "116") (name "Net-(D142-PadA)") (class "Default")
      (node (ref "D142") (pin "A") (pinfunction "A_A") (pintype "passive"))
      (node (ref "D143") (pin "C") (pinfunction "C_C") (pintype "passive"))
    )
    (net (code "117") (name "Net-(D143-PadA)") (class "Default")
      (node (ref "D143") (pin "A") (pinfunction "A_A") (pintype "passive"))
      (node (ref "D144") (pin "C") (pinfunction "C_C") (pintype "passive"))
    )
    (net (code "118") (name "Net-(D185-PadA)") (class "Default")
      (node (ref "D185") (pin "A") (pinfunction "A_A") (pintype "passive"))
      (node (ref "D186") (pin "C") (pinfunction "C_C") (pintype "passive"))
    )
    (net (code "119") (name "Net-(D186-PadA)") (class "Default")
      (node (ref "D186") (pin "A") (pinfunction "A_A") (pintype "passive"))
      (node (ref "D187") (pin "C") (pinfunction "C_C") (pintype "passive"))
    )
    (net (code "120") (name "Net-(D187-PadA)") (class "Default")
      (node (ref "D187") (pin "A") (pinfunction "A_A") (pintype "passive"))
      (node (ref "D188") (pin "C") (pinfunction "C_C") (pintype "passive"))
    )
    (net (code "121") (name "Net-(T1A-P$2)") (class "Default")
      (node (ref "Q2") (pin "B") (pinfunction "B_B") (pintype "passive"))
      (node (ref "T1") (pin "1") (pinfunction "P$2_1") (pintype "passive"))
    )
    (net (code "122") (name "Net-(T1A-P$4)") (class "Default")
      (node (ref "C32") (pin "1") (pinfunction "1_1") (pintype "passive"))
      (node (ref "R129") (pin "1") (pinfunction "1_1") (pintype "passive"))
      (node (ref "T1") (pin "16") (pinfunction "P$4_16") (pintype "passive"))
    )
    (net (code "123") (name "Net-(T1A-P$7)") (class "Default")
      (node (ref "C30") (pin "2") (pinfunction "2_2") (pintype "passive"))
      (node (ref "D98") (pin "C") (pinfunction "C_C") (pintype "passive"))
      (node (ref "Q2") (pin "E") (pinfunction "E_E") (pintype "passive"))
      (node (ref "R118") (pin "2") (pinfunction "2_2") (pintype "passive"))
      (node (ref "R71") (pin "2") (pinfunction "2_2") (pintype "passive"))
      (node (ref "R72") (pin "2") (pinfunction "2_2") (pintype "passive"))
      (node (ref "R73") (pin "2") (pinfunction "2_2") (pintype "passive"))
      (node (ref "T1") (pin "2") (pinfunction "P$7_2") (pintype "passive"))
    )
    (net (code "124") (name "Net-(T1B-P$2)") (class "Default")
      (node (ref "Q3") (pin "B") (pinfunction "B_B") (pintype "passive"))
      (node (ref "T1") (pin "3") (pinfunction "P$2_3") (pintype "passive"))
    )
    (net (code "125") (name "Net-(T1B-P$4)") (class "Default")
      (node (ref "C24") (pin "1") (pinfunction "1_1") (pintype "passive"))
      (node (ref "R54") (pin "1") (pinfunction "1_1") (pintype "passive"))
      (node (ref "T1") (pin "14") (pinfunction "P$4_14") (pintype "passive"))
    )
    (net (code "126") (name "Net-(T1B-P$7)") (class "Default")
      (node (ref "D63") (pin "C") (pinfunction "C_C") (pintype "passive"))
      (node (ref "Q3") (pin "E") (pinfunction "E_E") (pintype "passive"))
      (node (ref "R55") (pin "1") (pinfunction "1_1") (pintype "passive"))
      (node (ref "R56") (pin "2") (pinfunction "2_2") (pintype "passive"))
      (node (ref "T1") (pin "4") (pinfunction "P$7_4") (pintype "passive"))
    )
    (net (code "127") (name "Net-(T1D-P$2)") (class "Default")
      (node (ref "Q1") (pin "B") (pinfunction "B_B") (pintype "passive"))
      (node (ref "T1") (pin "7") (pinfunction "P$2_7") (pintype "passive"))
    )
    (net (code "128") (name "Net-(T1D-P$4)") (class "Default")
      (node (ref "C29") (pin "1") (pinfunction "1_1") (pintype "passive"))
      (node (ref "R31") (pin "1") (pinfunction "1_1") (pintype "passive"))
      (node (ref "T1") (pin "10") (pinfunction "P$4_10") (pintype "passive"))
    )
    (net (code "129") (name "Net-(T1D-P$7)") (class "Default")
      (node (ref "D17") (pin "C") (pinfunction "C_C") (pintype "passive"))
      (node (ref "Q1") (pin "E") (pinfunction "E_E") (pintype "passive"))
      (node (ref "R32") (pin "1") (pinfunction "1_1") (pintype "passive"))
      (node (ref "R33") (pin "2") (pinfunction "2_2") (pintype "passive"))
      (node (ref "R34") (pin "2") (pinfunction "2_2") (pintype "passive"))
      (node (ref "R35") (pin "2") (pinfunction "2_2") (pintype "passive"))
      (node (ref "R36") (pin "2") (pinfunction "2_2") (pintype "passive"))
      (node (ref "R37") (pin "2") (pinfunction "2_2") (pintype "passive"))
      (node (ref "R38") (pin "2") (pinfunction "2_2") (pintype "passive"))
      (node (ref "R39") (pin "2") (pinfunction "2_2") (pintype "passive"))
      (node (ref "R40") (pin "2") (pinfunction "2_2") (pintype "passive"))
      (node (ref "R41") (pin "2") (pinfunction "2_2") (pintype "passive"))
      (node (ref "R42") (pin "2") (pinfunction "2_2") (pintype "passive"))
      (node (ref "R43") (pin "2") (pinfunction "2_2") (pintype "passive"))
      (node (ref "R44") (pin "2") (pinfunction "2_2") (pintype "passive"))
      (node (ref "R45") (pin "2") (pinfunction "2_2") (pintype "passive"))
      (node (ref "R46") (pin "2") (pinfunction "2_2") (pintype "passive"))
      (node (ref "R47") (pin "2") (pinfunction "2_2") (pintype "passive"))
      (node (ref "R48") (pin "2") (pinfunction "2_2") (pintype "passive"))
      (node (ref "R49") (pin "2") (pinfunction "2_2") (pintype "passive"))
      (node (ref "R50") (pin "2") (pinfunction "2_2") (pintype "passive"))
      (node (ref "R51") (pin "2") (pinfunction "2_2") (pintype "passive"))
      (node (ref "R52") (pin "2") (pinfunction "2_2") (pintype "passive"))
      (node (ref "T1") (pin "8") (pinfunction "P$7_8") (pintype "passive"))
    )
    (net (code "130") (name "Net-(U$2A-1)") (class "Default")
      (node (ref "R55") (pin "2") (pinfunction "2_2") (pintype "passive"))
      (node (ref "U$2") (pin "AA1") (pinfunction "1_AA1") (pintype "bidirectional"))
    )
    (net (code "131") (name "Net-(U$2C-1)") (class "Default")
      (node (ref "R32") (pin "2") (pinfunction "2_2") (pintype "passive"))
      (node (ref "U$2") (pin "AB1") (pinfunction "1_AB1") (pintype "bidirectional"))
    )
    (net (code "132") (name "Net-(U$2DE-1)") (class "Default")
      (node (ref "R74") (pin "2") (pinfunction "2_2") (pintype "passive"))
      (node (ref "U$2") (pin "DA1") (pinfunction "1_DA1") (pintype "bidirectional"))
    )
    (net (code "133") (name "VCC") (class "Default")
      (node (ref "C10") (pin "1") (pinfunction "1_1") (pintype "passive"))
      (node (ref "C11") (pin "+") (pinfunction "+_+") (pintype "passive"))
      (node (ref "C12") (pin "+") (pinfunction "+_+") (pintype "passive"))
      (node (ref "C16") (pin "1") (pinfunction "1_1") (pintype "passive"))
      (node (ref "C18") (pin "1") (pinfunction "1_1") (pintype "passive"))
      (node (ref "C19") (pin "+") (pinfunction "+_+") (pintype "passive"))
      (node (ref "C22") (pin "1") (pinfunction "1_1") (pintype "passive"))
      (node (ref "C25") (pin "1") (pinfunction "1_1") (pintype "passive"))
      (node (ref "C26") (pin "+") (pinfunction "+_+") (pintype "passive"))
      (node (ref "C7") (pin "1") (pinfunction "1_1") (pintype "passive"))
      (node (ref "D16") (pin "C") (pinfunction "C_C") (pintype "passive"))
      (node (ref "D17") (pin "A") (pinfunction "A_A") (pintype "passive"))
      (node (ref "D62") (pin "C") (pinfunction "C_C") (pintype "passive"))
      (node (ref "D63") (pin "A") (pinfunction "A_A") (pintype "passive"))
      (node (ref "D96") (pin "C") (pinfunction "C_C") (pintype "passive"))
      (node (ref "R1") (pin "2") (pinfunction "2_2") (pintype "passive"))
      (node (ref "R11") (pin "2") (pinfunction "2_2") (pintype "passive"))
      (node (ref "R125") (pin "2") (pinfunction "2_2") (pintype "passive"))
      (node (ref "R126") (pin "2") (pinfunction "2_2") (pintype "passive"))
      (node (ref "R129") (pin "2") (pinfunction "2_2") (pintype "passive"))
      (node (ref "R13") (pin "2") (pinfunction "2_2") (pintype "passive"))
      (node (ref "R15") (pin "2") (pinfunction "2_2") (pintype "passive"))
      (node (ref "R17") (pin "2") (pinfunction "2_2") (pintype "passive"))
      (node (ref "R19") (pin "2") (pinfunction "2_2") (pintype "passive"))
      (node (ref "R21") (pin "2") (pinfunction "2_2") (pintype "passive"))
      (node (ref "R23") (pin "2") (pinfunction "2_2") (pintype "passive"))
      (node (ref "R25") (pin "2") (pinfunction "2_2") (pintype "passive"))
      (node (ref "R27") (pin "2") (pinfunction "2_2") (pintype "passive"))
      (node (ref "R29") (pin "2") (pinfunction "2_2") (pintype "passive"))
      (node (ref "R3") (pin "2") (pinfunction "2_2") (pintype "passive"))
      (node (ref "R31") (pin "2") (pinfunction "2_2") (pintype "passive"))
      (node (ref "R5") (pin "2") (pinfunction "2_2") (pintype "passive"))
      (node (ref "R54") (pin "2") (pinfunction "2_2") (pintype "passive"))
      (node (ref "R7") (pin "2") (pinfunction "2_2") (pintype "passive"))
      (node (ref "R9") (pin "2") (pinfunction "2_2") (pintype "passive"))
      (node (ref "U$2") (pin "AA2") (pinfunction "1_AA2") (pintype "bidirectional"))
      (node (ref "U$2") (pin "BA2") (pinfunction "1_BA2") (pintype "bidirectional"))
      (node (ref "U$2") (pin "CA2") (pinfunction "1_CA2") (pintype "bidirectional"))
    )
  )
)
